# Spine14v1.net
KiCad netlist of a schematic drawn in EAGLE
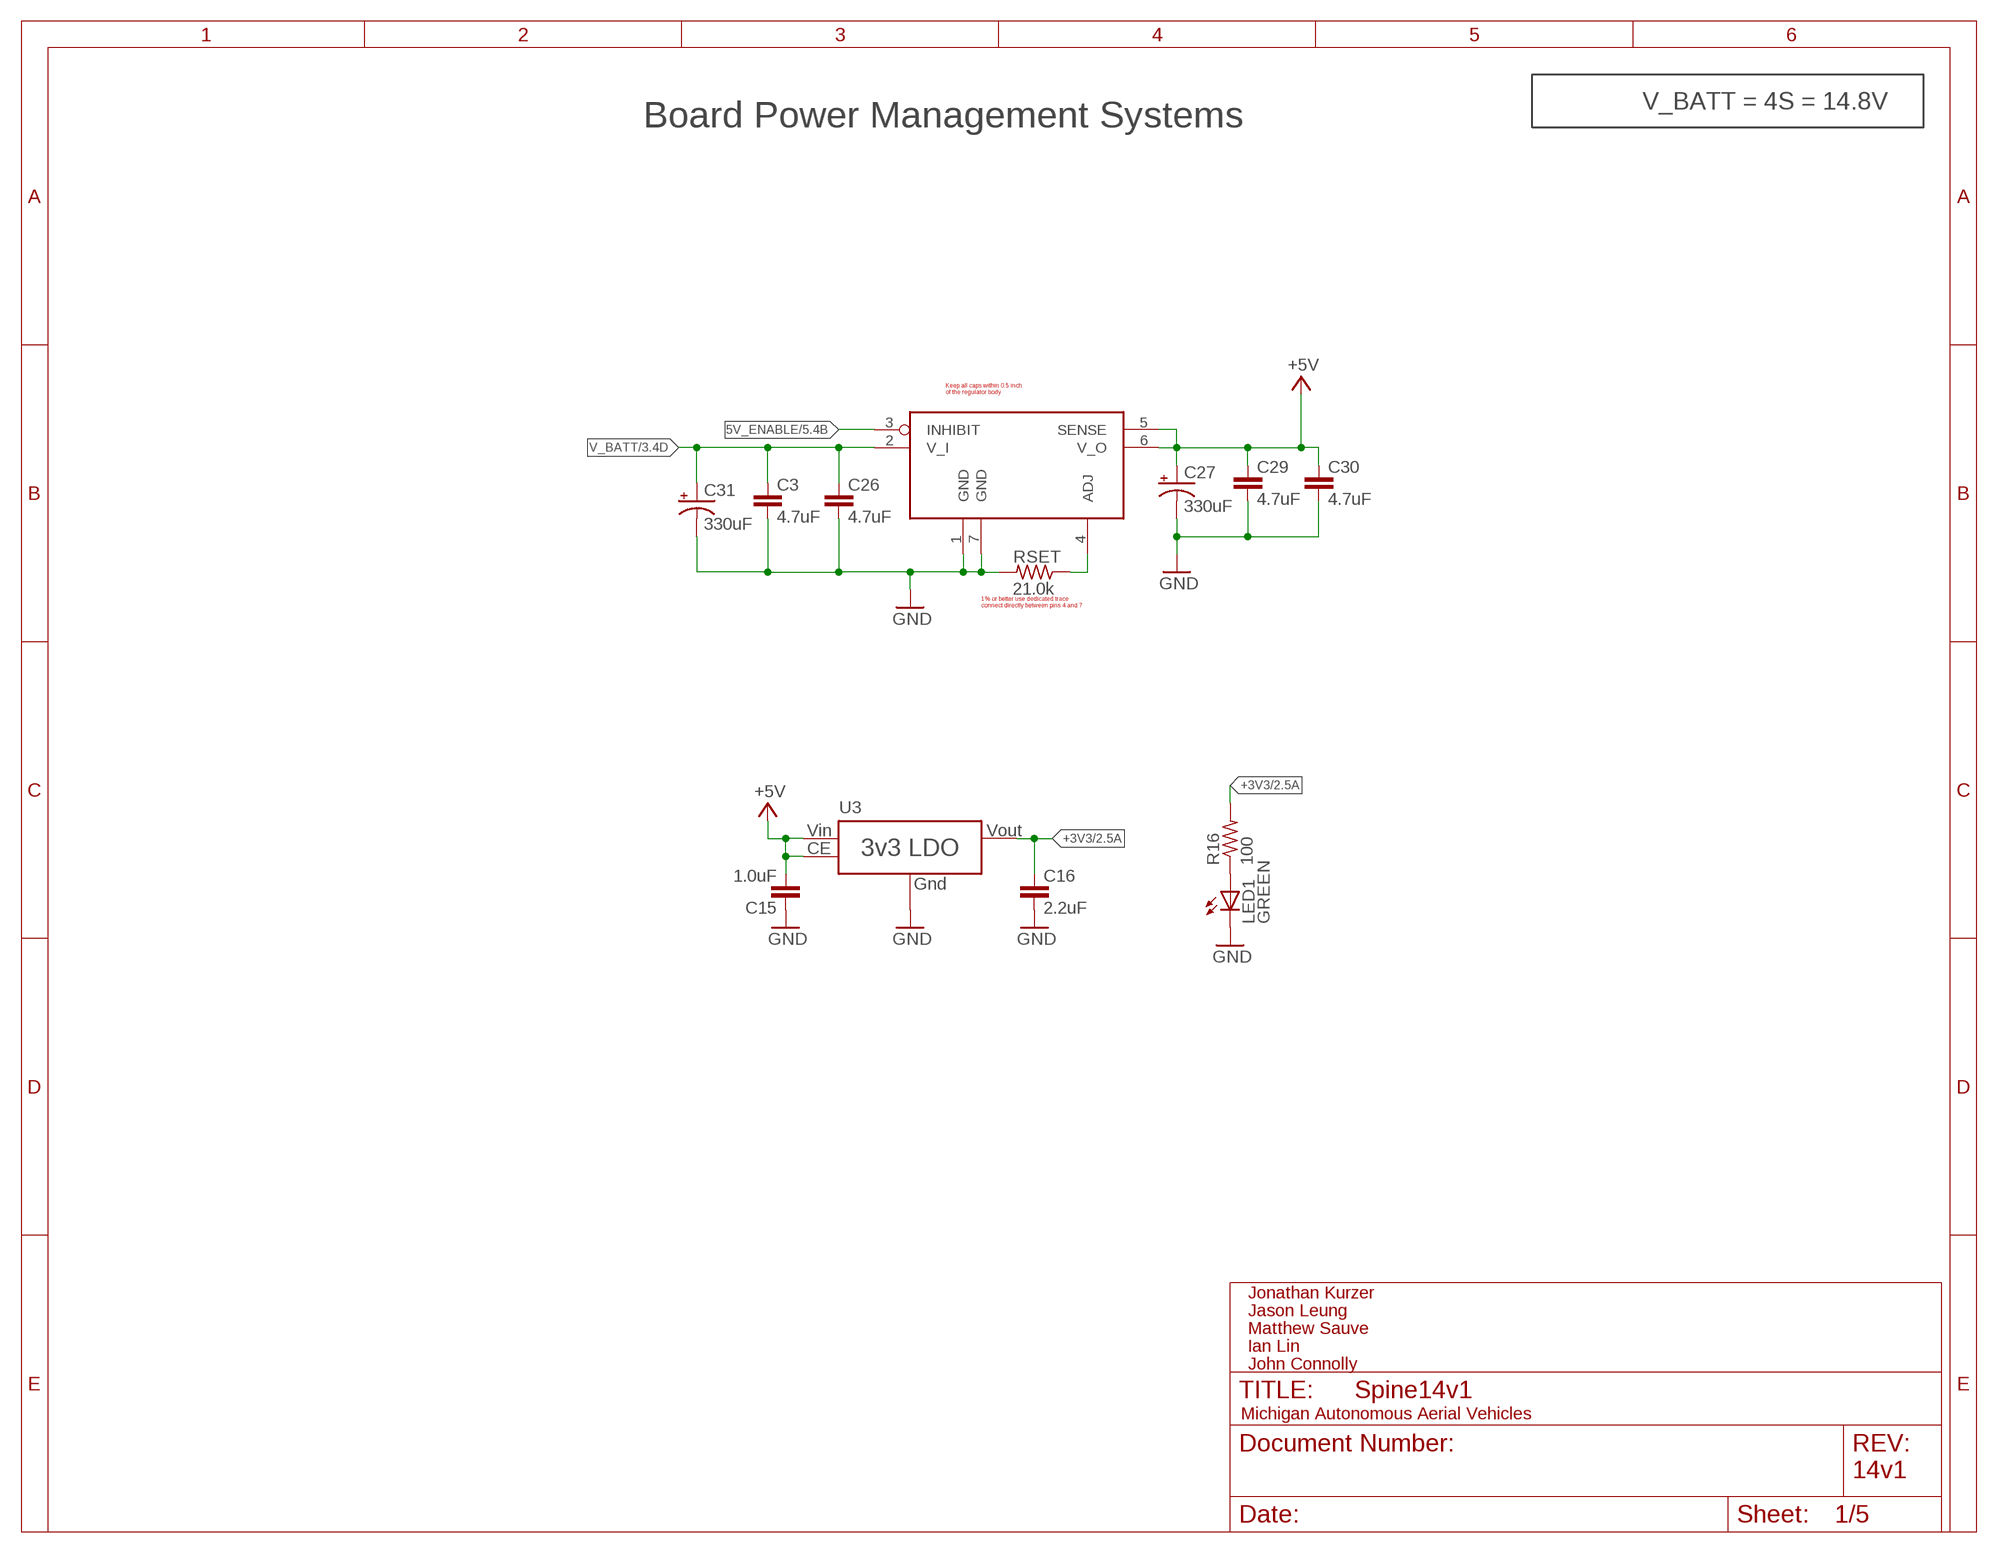
[diagram p0: schematic, sheet 1]
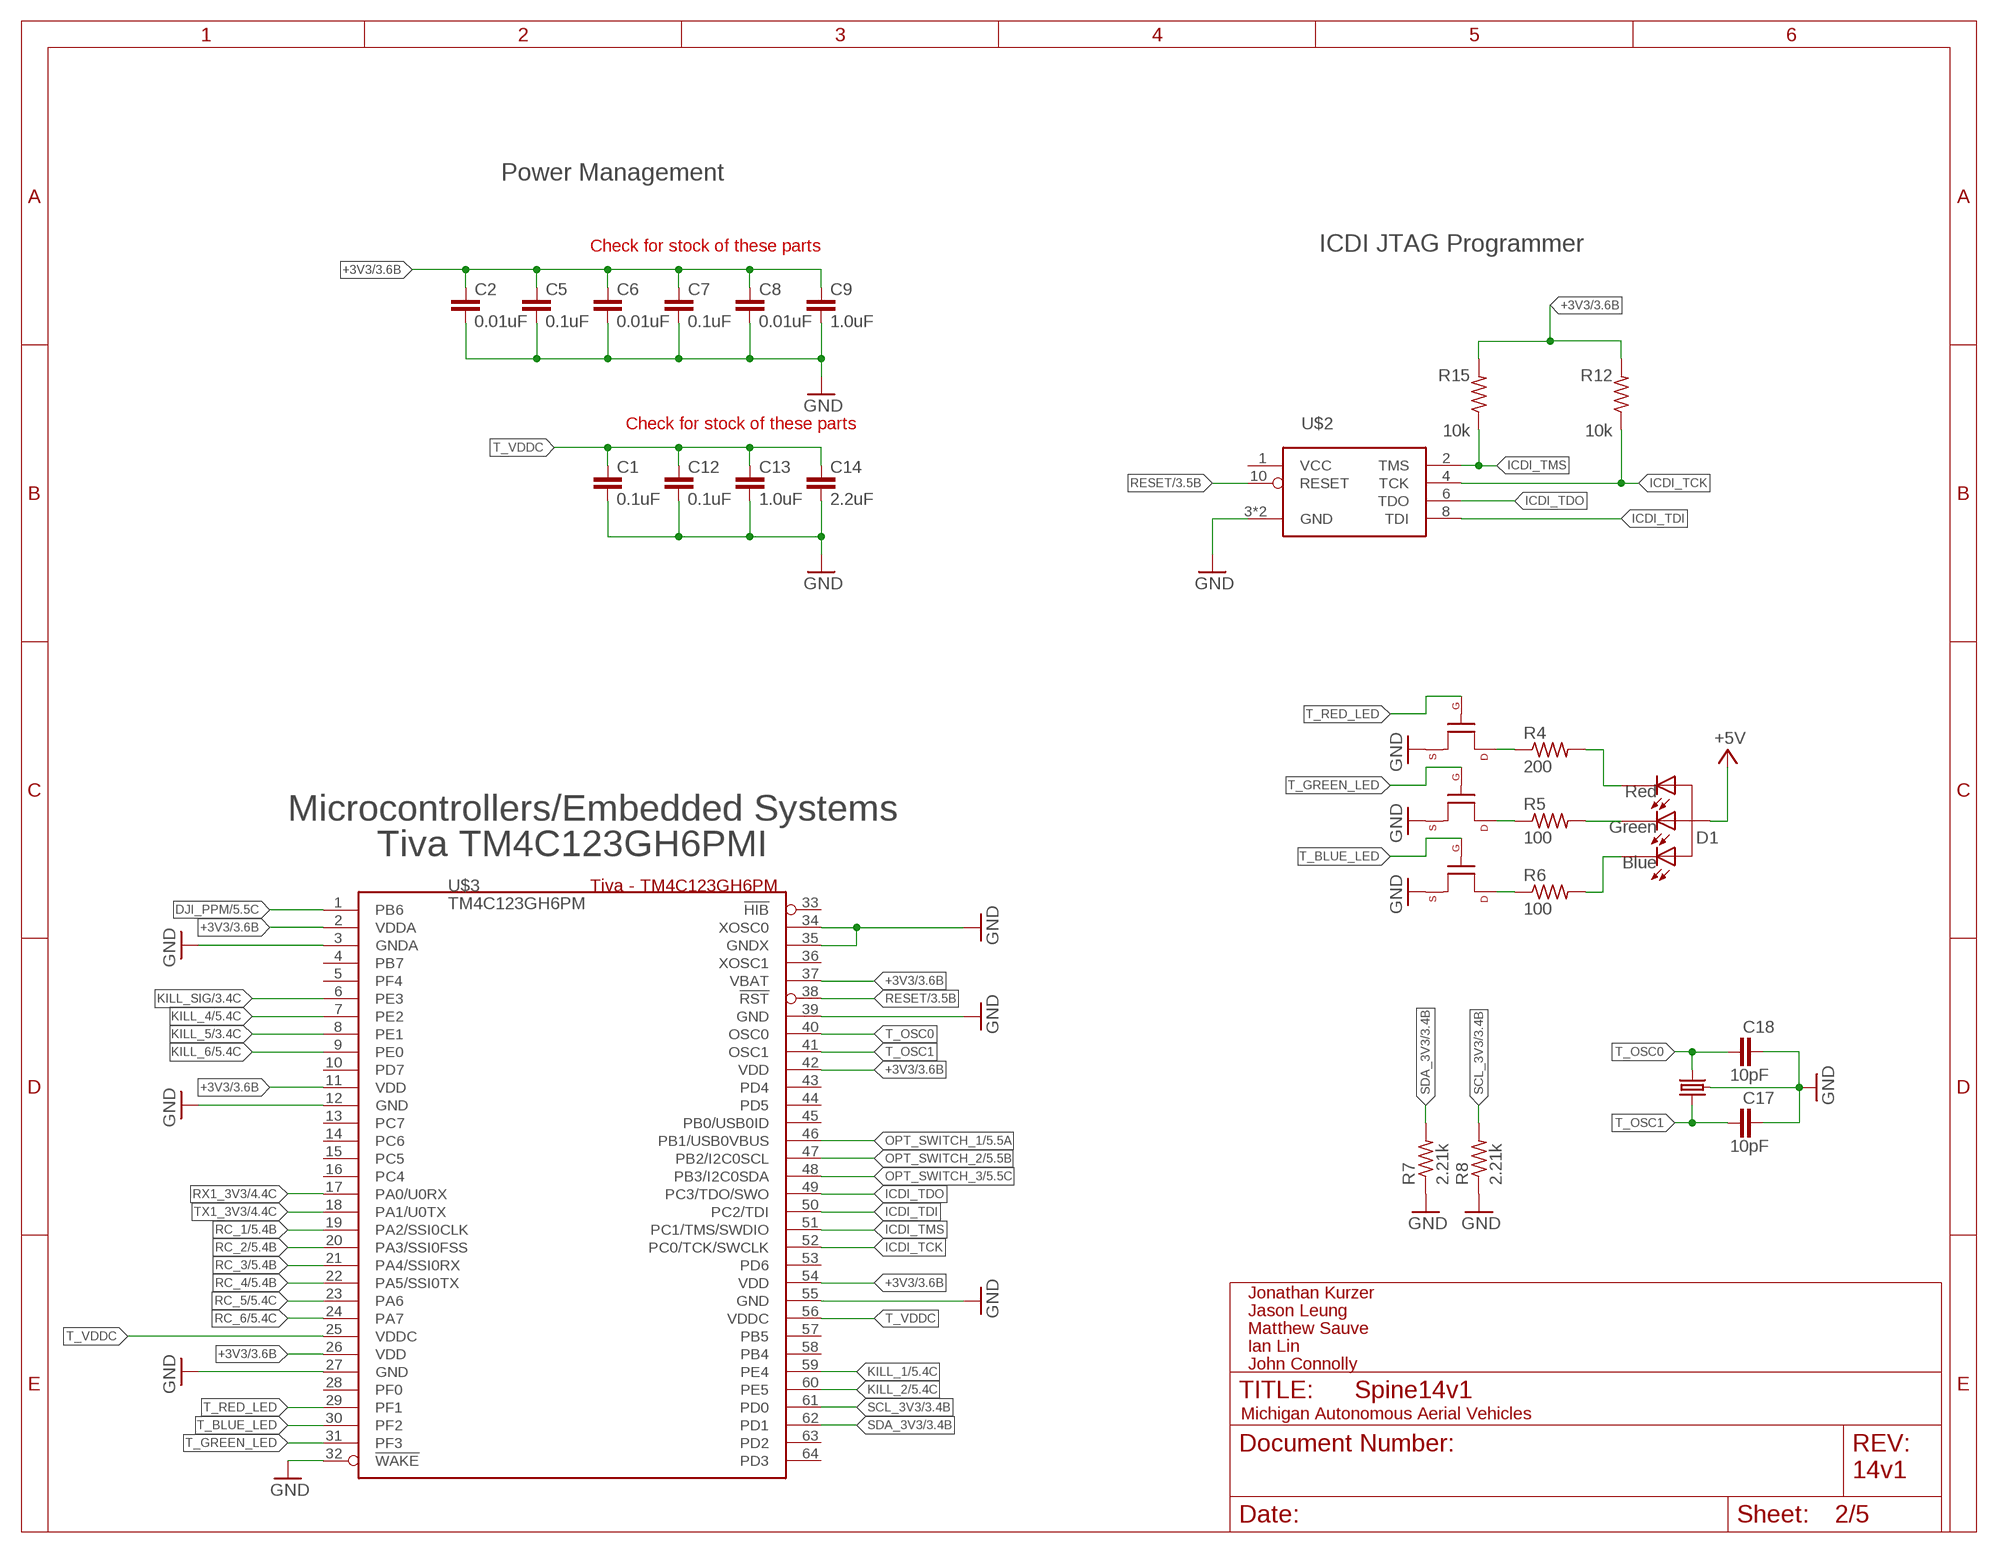
[diagram p1: schematic, sheet 2]
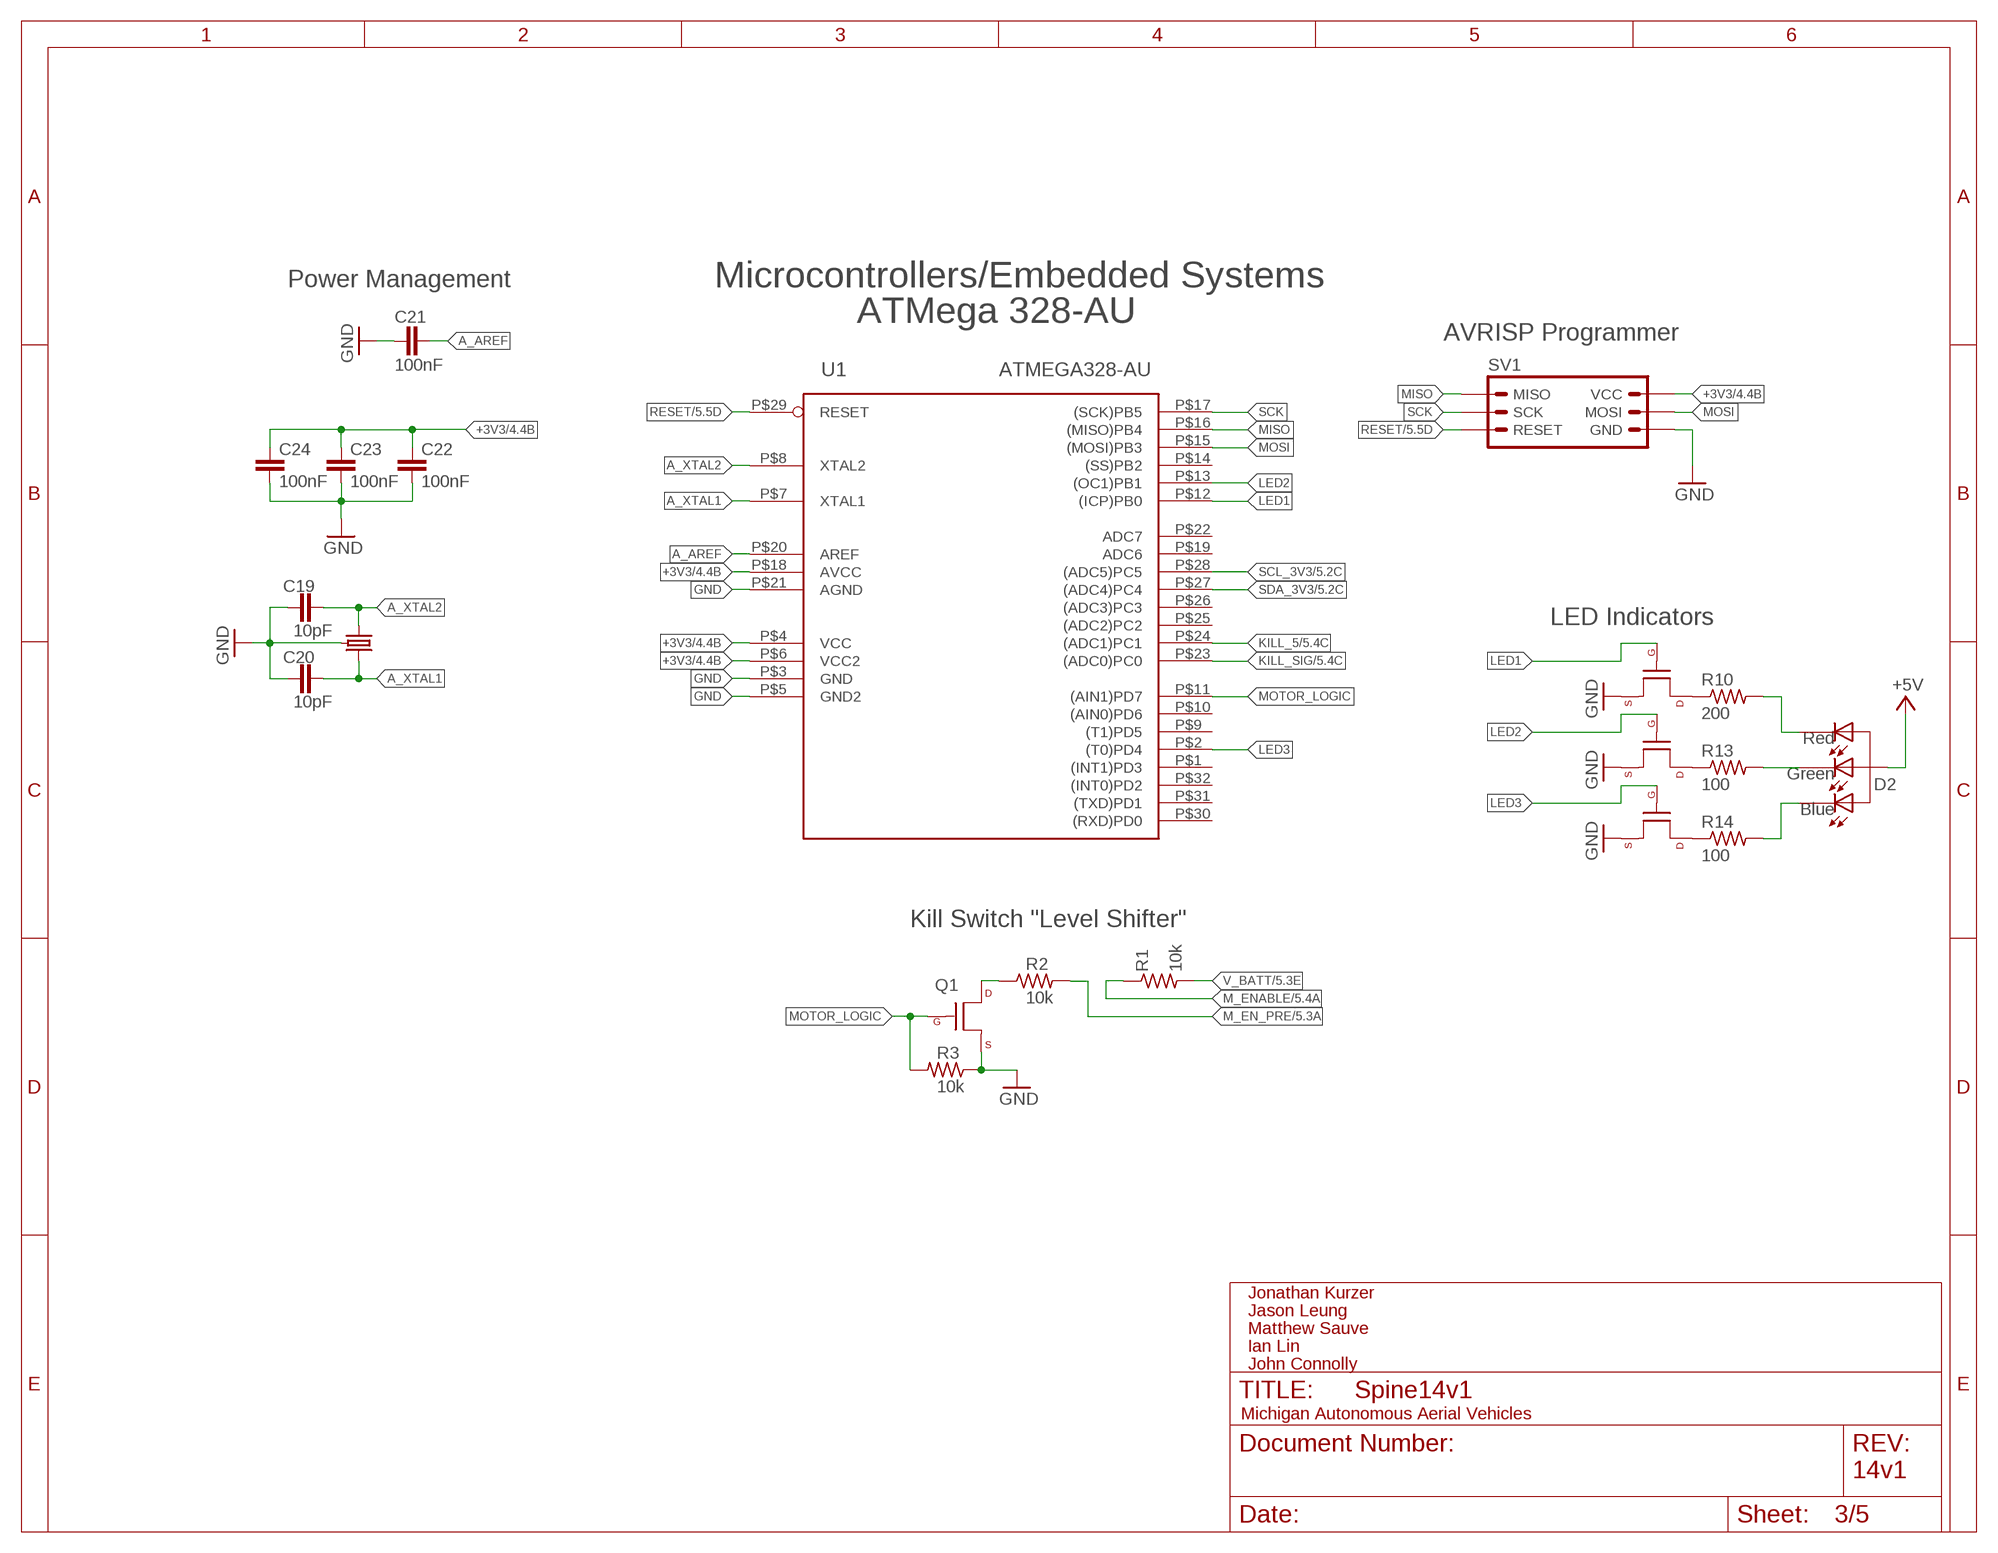
[diagram p2: schematic, sheet 3]
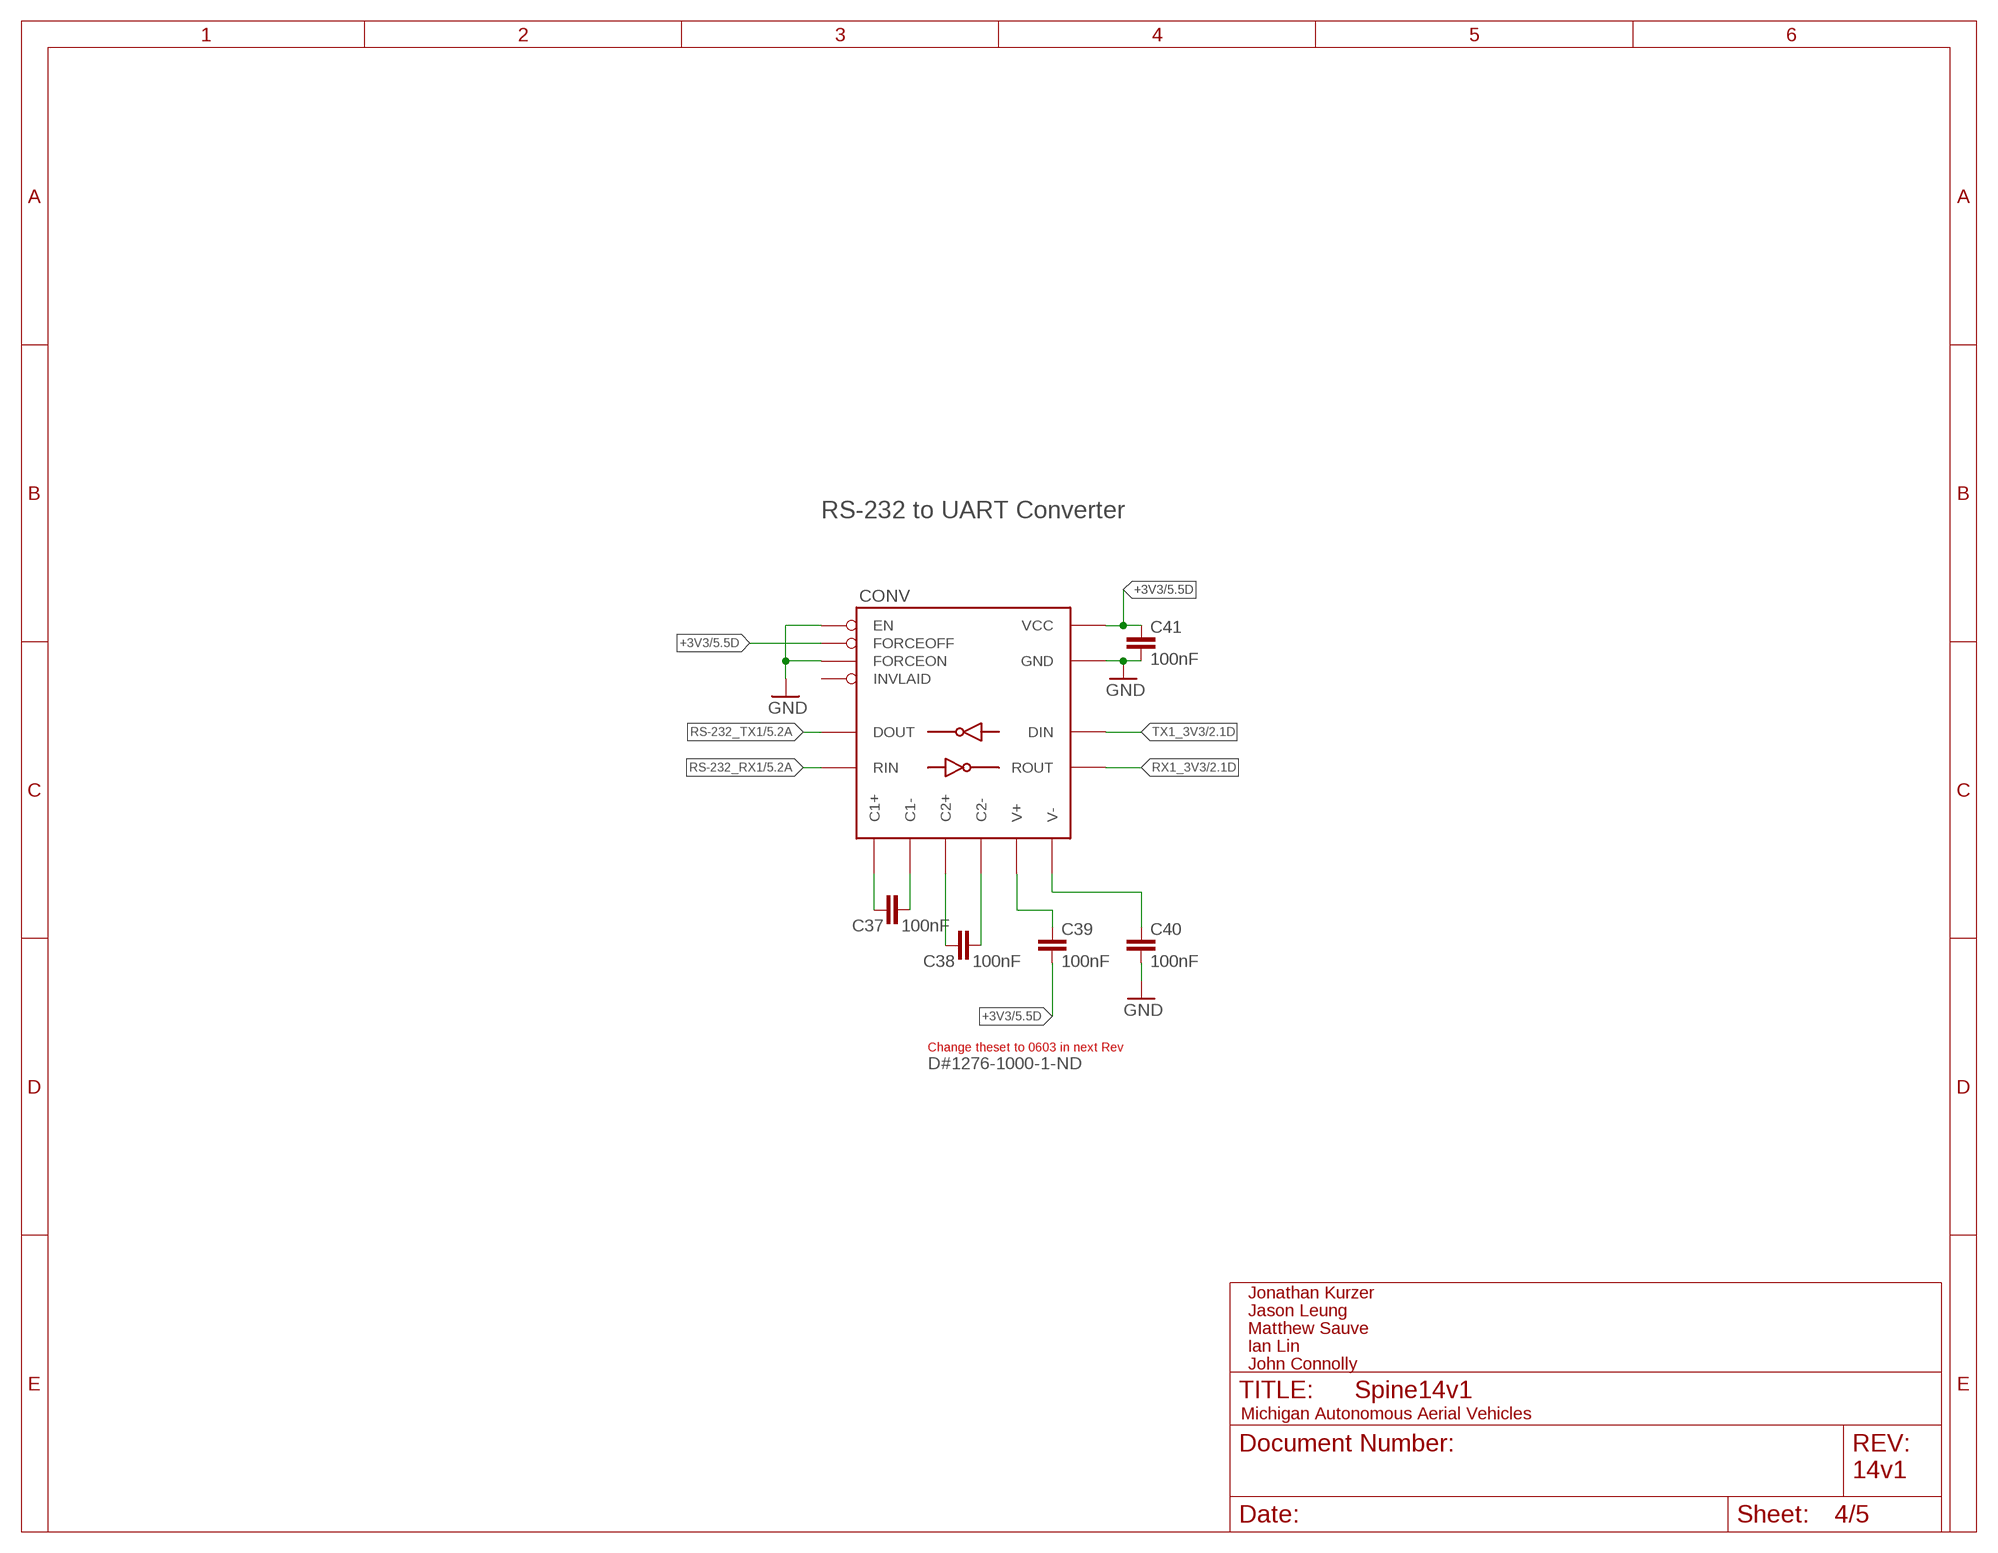
[diagram p3: schematic, sheet 4]
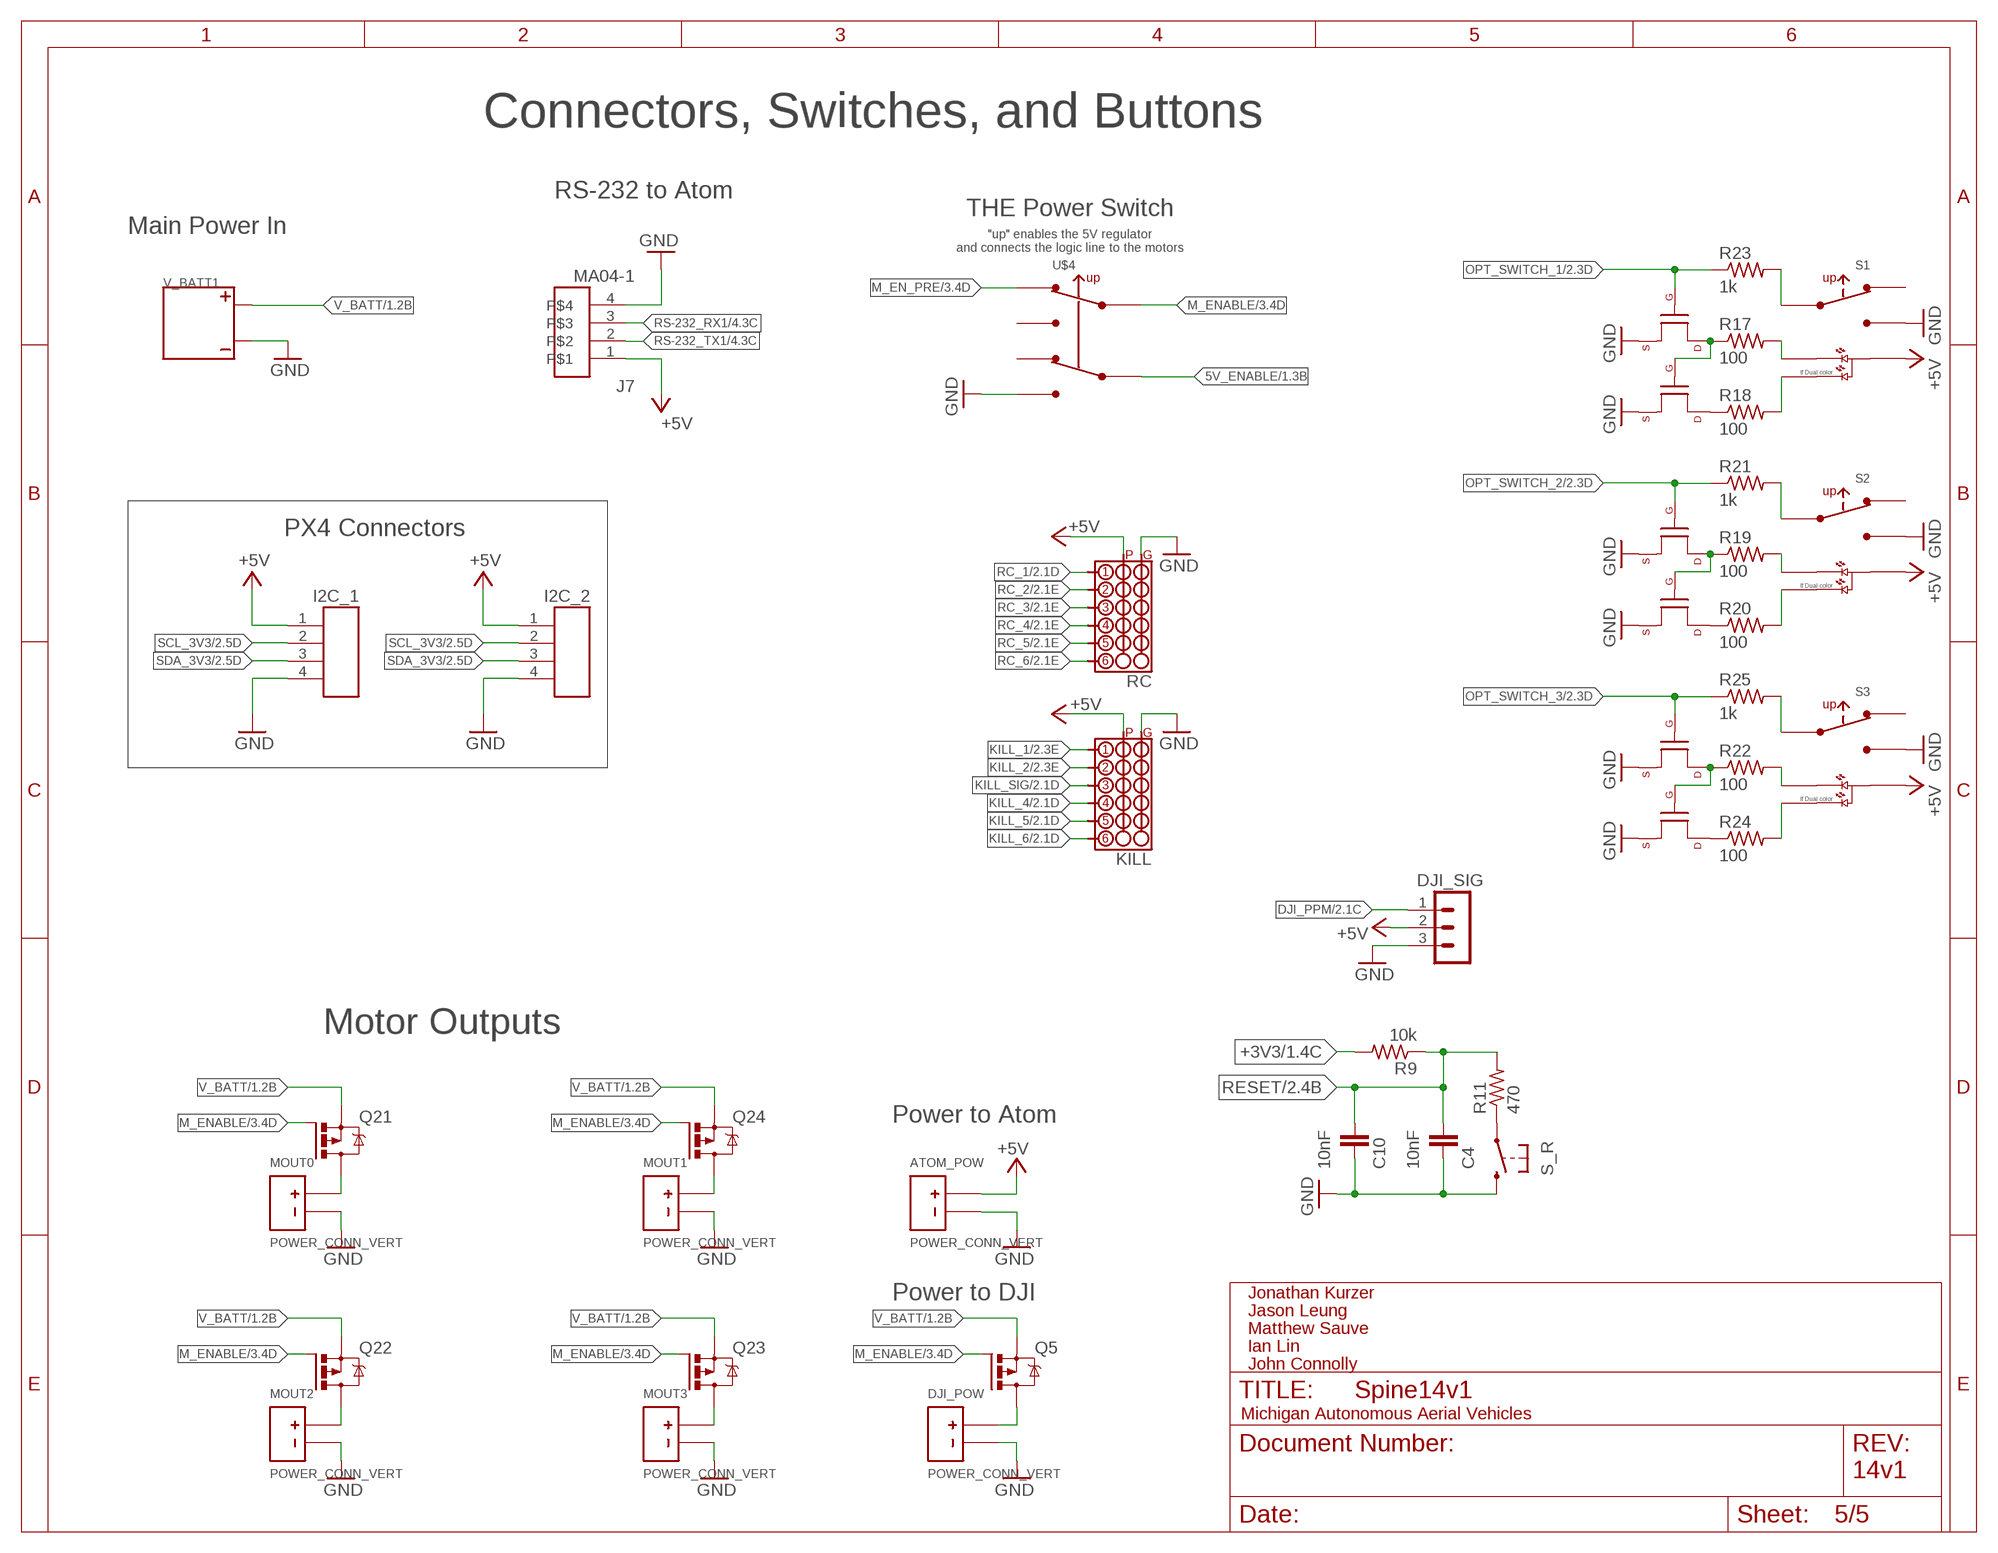
[diagram p4: schematic, sheet 5]

(export (version "E")
  (design (tool "Eeschema 10.0.6"))
  (components
    (comp (ref "C37")
      (value "100nF")
      (footprint "eagle-import:C0603")
      (fields (field (name "DIGIKEY#") "1276-1000-1-ND"))
      (libsource (lib "eagle-import") (part "C-EUC0603"))
    )
    (comp (ref "C38")
      (value "100nF")
      (footprint "eagle-import:C0805")
      (libsource (lib "eagle-import") (part "C-EUC0805"))
    )
    (comp (ref "C39")
      (value "100nF")
      (footprint "eagle-import:C0805")
      (libsource (lib "eagle-import") (part "C-EUC0805"))
    )
    (comp (ref "C40")
      (value "100nF")
      (footprint "eagle-import:C0805")
      (libsource (lib "eagle-import") (part "C-EUC0805"))
    )
    (comp (ref "C41")
      (value "100nF")
      (footprint "eagle-import:C0603")
      (fields (field (name "DIGIKEY#") "1276-1000-1-ND"))
      (libsource (lib "eagle-import") (part "C-EUC0603"))
    )
    (comp (ref "CONV")
      (value "MAX3221-RS232")
      (footprint "eagle-import:16-TSSOP")
      (fields (field (name "DIGIKEY#") "296-19825-1-ND"))
      (libsource (lib "eagle-import") (part "MAX3221-RS232"))
    )
    (comp (ref "ATOM_POW")
      (value "POWER_CONN_VERT")
      (footprint "eagle-import:POWER_CONN")
      (libsource (lib "eagle-import") (part "POWER_CONN_VERT"))
    )
    (comp (ref "C4")
      (value "10nF")
      (footprint "eagle-import:C0603")
      (libsource (lib "eagle-import") (part "C-EUC0603"))
    )
    (comp (ref "C10")
      (value "10nF")
      (footprint "eagle-import:C0603")
      (libsource (lib "eagle-import") (part "C-EUC0603"))
    )
    (comp (ref "DJI_POW")
      (value "POWER_CONN_VERT")
      (footprint "eagle-import:POWER_CONN")
      (libsource (lib "eagle-import") (part "POWER_CONN_VERT"))
    )
    (comp (ref "DJI_SIG")
      (value "MA03-1")
      (footprint "eagle-import:MA03-1")
      (libsource (lib "eagle-import") (part "MA03-1"))
    )
    (comp (ref "I2C_1")
      (value "CONN_HEADER_4POS_RIGHT_ANGLE_I2C")
      (footprint "eagle-import:CONN_HEADER_4POS_1.25MM_SMD")
      (fields (field (name "CONTACT") "D#H12151CT-ND"))
      (libsource (lib "eagle-import") (part "CONN_HEADER_4POS_RIGHT_ANGLE_I2C"))
    )
    (comp (ref "I2C_2")
      (value "CONN_HEADER_4POS_RIGHT_ANGLE_I2C")
      (footprint "eagle-import:CONN_HEADER_4POS_1.25MM_SMD")
      (fields (field (name "CONTACT") "D#H12151CT-ND"))
      (libsource (lib "eagle-import") (part "CONN_HEADER_4POS_RIGHT_ANGLE_I2C"))
    )
    (comp (ref "J7")
      (value "MA04-1")
      (footprint "eagle-import:MA-04-SMD")
      (libsource (lib "eagle-import") (part "MA04-1"))
    )
    (comp (ref "KILL")
      (value "RC_RECIEVER_RECEP")
      (footprint "eagle-import:RC_RECIEVER_RECEP")
      (libsource (lib "eagle-import") (part "RC_RECIEVER_RECEP"))
    )
    (comp (ref "MOUT0")
      (value "POWER_CONN_VERT")
      (footprint "eagle-import:POWER_CONN")
      (libsource (lib "eagle-import") (part "POWER_CONN_VERT"))
    )
    (comp (ref "MOUT1")
      (value "POWER_CONN_VERT")
      (footprint "eagle-import:POWER_CONN")
      (libsource (lib "eagle-import") (part "POWER_CONN_VERT"))
    )
    (comp (ref "MOUT2")
      (value "POWER_CONN_VERT")
      (footprint "eagle-import:POWER_CONN")
      (libsource (lib "eagle-import") (part "POWER_CONN_VERT"))
    )
    (comp (ref "MOUT3")
      (value "POWER_CONN_VERT")
      (footprint "eagle-import:POWER_CONN")
      (libsource (lib "eagle-import") (part "POWER_CONN_VERT"))
    )
    (comp (ref "Q5")
      (value "P-MOSFET-SO8POWER-PAK")
      (footprint "eagle-import:SO-8_POWER-PAK")
      (libsource (lib "eagle-import") (part "P-MOSFET-SO8POWER-PAK"))
    )
    (comp (ref "Q9")
      (value "MOSFET-NCHANNELSMD")
      (footprint "eagle-import:SOT23-3")
      (fields (field (name "DIGIKEY#") "BSN20-7DICT-ND"))
      (libsource (lib "eagle-import") (part "MOSFET-NCHANNELSMD"))
    )
    (comp (ref "Q10")
      (value "MOSFET-NCHANNELSMD")
      (footprint "eagle-import:SOT23-3")
      (fields (field (name "DIGIKEY#") "BSN20-7DICT-ND"))
      (libsource (lib "eagle-import") (part "MOSFET-NCHANNELSMD"))
    )
    (comp (ref "Q11")
      (value "MOSFET-NCHANNELSMD")
      (footprint "eagle-import:SOT23-3")
      (fields (field (name "DIGIKEY#") "BSN20-7DICT-ND"))
      (libsource (lib "eagle-import") (part "MOSFET-NCHANNELSMD"))
    )
    (comp (ref "Q12")
      (value "MOSFET-NCHANNELSMD")
      (footprint "eagle-import:SOT23-3")
      (fields (field (name "DIGIKEY#") "BSN20-7DICT-ND"))
      (libsource (lib "eagle-import") (part "MOSFET-NCHANNELSMD"))
    )
    (comp (ref "Q13")
      (value "MOSFET-NCHANNELSMD")
      (footprint "eagle-import:SOT23-3")
      (fields (field (name "DIGIKEY#") "BSN20-7DICT-ND"))
      (libsource (lib "eagle-import") (part "MOSFET-NCHANNELSMD"))
    )
    (comp (ref "Q14")
      (value "MOSFET-NCHANNELSMD")
      (footprint "eagle-import:SOT23-3")
      (fields (field (name "DIGIKEY#") "BSN20-7DICT-ND"))
      (libsource (lib "eagle-import") (part "MOSFET-NCHANNELSMD"))
    )
    (comp (ref "Q21")
      (value "P-MOSFET-SO8POWER-PAK")
      (footprint "eagle-import:SO-8_POWER-PAK")
      (libsource (lib "eagle-import") (part "P-MOSFET-SO8POWER-PAK"))
    )
    (comp (ref "Q22")
      (value "P-MOSFET-SO8POWER-PAK")
      (footprint "eagle-import:SO-8_POWER-PAK")
      (libsource (lib "eagle-import") (part "P-MOSFET-SO8POWER-PAK"))
    )
    (comp (ref "Q23")
      (value "P-MOSFET-SO8POWER-PAK")
      (footprint "eagle-import:SO-8_POWER-PAK")
      (libsource (lib "eagle-import") (part "P-MOSFET-SO8POWER-PAK"))
    )
    (comp (ref "Q24")
      (value "P-MOSFET-SO8POWER-PAK")
      (footprint "eagle-import:SO-8_POWER-PAK")
      (libsource (lib "eagle-import") (part "P-MOSFET-SO8POWER-PAK"))
    )
    (comp (ref "R9")
      (value "10k")
      (footprint "eagle-import:R0603")
      (libsource (lib "eagle-import") (part "R-USR0603"))
    )
    (comp (ref "R11")
      (value "470")
      (footprint "eagle-import:R0603")
      (libsource (lib "eagle-import") (part "R-USR0603"))
    )
    (comp (ref "R17")
      (value "100")
      (footprint "eagle-import:R0603")
      (libsource (lib "eagle-import") (part "R-USR0603"))
    )
    (comp (ref "R18")
      (value "100")
      (footprint "eagle-import:R0603")
      (libsource (lib "eagle-import") (part "R-USR0603"))
    )
    (comp (ref "R19")
      (value "100")
      (footprint "eagle-import:R0603")
      (libsource (lib "eagle-import") (part "R-USR0603"))
    )
    (comp (ref "R20")
      (value "100")
      (footprint "eagle-import:R0603")
      (libsource (lib "eagle-import") (part "R-USR0603"))
    )
    (comp (ref "R21")
      (value "1k")
      (footprint "eagle-import:R0603")
      (libsource (lib "eagle-import") (part "R-USR0603"))
    )
    (comp (ref "R22")
      (value "100")
      (footprint "eagle-import:R0603")
      (libsource (lib "eagle-import") (part "R-USR0603"))
    )
    (comp (ref "R23")
      (value "1k")
      (footprint "eagle-import:R0603")
      (libsource (lib "eagle-import") (part "R-USR0603"))
    )
    (comp (ref "R24")
      (value "100")
      (footprint "eagle-import:R0603")
      (libsource (lib "eagle-import") (part "R-USR0603"))
    )
    (comp (ref "R25")
      (value "1k")
      (footprint "eagle-import:R0603")
      (libsource (lib "eagle-import") (part "R-USR0603"))
    )
    (comp (ref "RC")
      (value "RC_RECIEVER_RECEP")
      (footprint "eagle-import:RC_RECIEVER_RECEP")
      (libsource (lib "eagle-import") (part "RC_RECIEVER_RECEP"))
    )
    (comp (ref "S1")
      (value "SWITCH_SPDT_ILUMINATED_2COLOR_VERT_ILLUMINATED")
      (footprint "eagle-import:NKK_VERT_SWITCH_6PIN")
      (libsource (lib "eagle-import") (part "SWITCH_SPDT_ILUMINATED_2COLOR_VERT_ILLUMINATED"))
    )
    (comp (ref "S2")
      (value "SWITCH_SPDT_ILUMINATED_2COLOR_VERT_ILLUMINATED")
      (footprint "eagle-import:NKK_VERT_SWITCH_6PIN")
      (libsource (lib "eagle-import") (part "SWITCH_SPDT_ILUMINATED_2COLOR_VERT_ILLUMINATED"))
    )
    (comp (ref "S3")
      (value "SWITCH_SPDT_ILUMINATED_2COLOR_VERT_ILLUMINATED")
      (footprint "eagle-import:NKK_VERT_SWITCH_6PIN")
      (libsource (lib "eagle-import") (part "SWITCH_SPDT_ILUMINATED_2COLOR_VERT_ILLUMINATED"))
    )
    (comp (ref "S_R")
      (value "TACT_BUTTONSMD")
      (footprint "eagle-import:TACT-MOM-SMD")
      (libsource (lib "eagle-import") (part "TACT_BUTTONSMD"))
    )
    (comp (ref "U$4")
      (value "JON_LIB_SWITCH_DPDT")
      (footprint "eagle-import:JON_LIB_SWITCH_VERT_DPDT")
      (libsource (lib "eagle-import") (part "JON_LIB_SWITCH_DPDT"))
    )
    (comp (ref "V_BATT1")
      (value "BATT-CONN-50A_MINI-FIT-SR_THRU-HOLE")
      (footprint "eagle-import:BATT-CONN-50A")
      (libsource (lib "eagle-import") (part "BATT-CONN-50A_MINI-FIT-SR_THRU-HOLE"))
    )
    (comp (ref "C1")
      (value "0.1uF")
      (footprint "eagle-import:C0603")
      (libsource (lib "eagle-import") (part "C-EUC0603"))
    )
    (comp (ref "C2")
      (value "0.01uF")
      (footprint "eagle-import:C0603")
      (libsource (lib "eagle-import") (part "C-EUC0603"))
    )
    (comp (ref "C5")
      (value "0.1uF")
      (footprint "eagle-import:C0603")
      (libsource (lib "eagle-import") (part "C-EUC0603"))
    )
    (comp (ref "C6")
      (value "0.01uF")
      (footprint "eagle-import:C0603")
      (libsource (lib "eagle-import") (part "C-EUC0603"))
    )
    (comp (ref "C7")
      (value "0.1uF")
      (footprint "eagle-import:C0603")
      (libsource (lib "eagle-import") (part "C-EUC0603"))
    )
    (comp (ref "C8")
      (value "0.01uF")
      (footprint "eagle-import:C0603")
      (libsource (lib "eagle-import") (part "C-EUC0603"))
    )
    (comp (ref "C9")
      (value "1.0uF")
      (footprint "eagle-import:C0603")
      (libsource (lib "eagle-import") (part "C-EUC0603"))
    )
    (comp (ref "C12")
      (value "0.1uF")
      (footprint "eagle-import:C0603")
      (libsource (lib "eagle-import") (part "C-EUC0603"))
    )
    (comp (ref "C13")
      (value "1.0uF")
      (footprint "eagle-import:C0805")
      (libsource (lib "eagle-import") (part "C-EUC0805"))
    )
    (comp (ref "C14")
      (value "2.2uF")
      (footprint "eagle-import:C0805")
      (libsource (lib "eagle-import") (part "C-EUC0805"))
    )
    (comp (ref "C17")
      (value "10pF")
      (footprint "eagle-import:C0603")
      (fields (field (name "DIGIKEY#") "399-1049-1-ND"))
      (libsource (lib "eagle-import") (part "C-EUC0603"))
    )
    (comp (ref "C18")
      (value "10pF")
      (footprint "eagle-import:C0603")
      (fields (field (name "DIGIKEY#") "399-1049-1-ND"))
      (libsource (lib "eagle-import") (part "C-EUC0603"))
    )
    (comp (ref "D1")
      (value "LED_RGB_CA")
      (footprint "eagle-import:LED_RGB_0606")
      (libsource (lib "eagle-import") (part "LED_RGB_CA"))
    )
    (comp (ref "Q2")
      (value "MOSFET-NCHANNELSMD")
      (footprint "eagle-import:SOT23-3")
      (fields (field (name "DIGIKEY#") "BSN20-7DICT-ND"))
      (libsource (lib "eagle-import") (part "MOSFET-NCHANNELSMD"))
    )
    (comp (ref "Q3")
      (value "MOSFET-NCHANNELSMD")
      (footprint "eagle-import:SOT23-3")
      (fields (field (name "DIGIKEY#") "BSN20-7DICT-ND"))
      (libsource (lib "eagle-import") (part "MOSFET-NCHANNELSMD"))
    )
    (comp (ref "Q4")
      (value "MOSFET-NCHANNELSMD")
      (footprint "eagle-import:SOT23-3")
      (fields (field (name "DIGIKEY#") "BSN20-7DICT-ND"))
      (libsource (lib "eagle-import") (part "MOSFET-NCHANNELSMD"))
    )
    (comp (ref "R4")
      (value "200")
      (footprint "eagle-import:R0603")
      (libsource (lib "eagle-import") (part "R-USR0603"))
    )
    (comp (ref "R5")
      (value "100")
      (footprint "eagle-import:R0603")
      (libsource (lib "eagle-import") (part "R-USR0603"))
    )
    (comp (ref "R6")
      (value "100")
      (footprint "eagle-import:R0603")
      (libsource (lib "eagle-import") (part "R-USR0603"))
    )
    (comp (ref "R7")
      (value "2.21k")
      (footprint "eagle-import:R0603")
      (libsource (lib "eagle-import") (part "R-USR0603"))
    )
    (comp (ref "R8")
      (value "2.21k")
      (footprint "eagle-import:R0603")
      (libsource (lib "eagle-import") (part "R-USR0603"))
    )
    (comp (ref "R12")
      (value "10k")
      (footprint "eagle-import:R0603")
      (libsource (lib "eagle-import") (part "R-USR0603"))
    )
    (comp (ref "R15")
      (value "10k")
      (footprint "eagle-import:R0603")
      (libsource (lib "eagle-import") (part "R-USR0603"))
    )
    (comp (ref "U$1")
      (value "CRYSTAL_403C11E16")
      (footprint "eagle-import:4-SMD-SWITCH")
      (libsource (lib "eagle-import") (part "CRYSTAL_403C11E16"))
    )
    (comp (ref "U$2")
      (value "JTAG-ARM_TC-10")
      (footprint "eagle-import:TC2050-IDC")
      (libsource (lib "eagle-import") (part "JTAG-ARM_TC-10"))
    )
    (comp (ref "U$3")
      (value "TM4C123GH6PM")
      (footprint "eagle-import:TM4C123GH6PM")
      (libsource (lib "eagle-import") (part "TM4C123GH6PM"))
    )
    (comp (ref "C19")
      (value "10pF")
      (footprint "eagle-import:C0603")
      (fields (field (name "DIGIKEY#") "399-1049-1-ND"))
      (libsource (lib "eagle-import") (part "C-EUC0603"))
    )
    (comp (ref "C20")
      (value "10pF")
      (footprint "eagle-import:C0603")
      (fields (field (name "DIGIKEY#") "399-1049-1-ND"))
      (libsource (lib "eagle-import") (part "C-EUC0603"))
    )
    (comp (ref "C21")
      (value "100nF")
      (footprint "eagle-import:C0603")
      (fields (field (name "DIGIKEY#") "1276-1000-1-ND"))
      (libsource (lib "eagle-import") (part "C-EUC0603"))
    )
    (comp (ref "C22")
      (value "100nF")
      (footprint "eagle-import:C0603")
      (fields (field (name "DIGIKEY#") "1276-1000-1-ND"))
      (libsource (lib "eagle-import") (part "C-EUC0603"))
    )
    (comp (ref "C23")
      (value "100nF")
      (footprint "eagle-import:C0603")
      (fields (field (name "DIGIKEY#") "1276-1000-1-ND"))
      (libsource (lib "eagle-import") (part "C-EUC0603"))
    )
    (comp (ref "C24")
      (value "100nF")
      (footprint "eagle-import:C0603")
      (fields (field (name "DIGIKEY#") "1276-1000-1-ND"))
      (libsource (lib "eagle-import") (part "C-EUC0603"))
    )
    (comp (ref "D2")
      (value "LED_RGB_CA")
      (footprint "eagle-import:LED_RGB_0606")
      (libsource (lib "eagle-import") (part "LED_RGB_CA"))
    )
    (comp (ref "Q1")
      (value "MOSFET-NCHANNELSMD")
      (footprint "eagle-import:SOT23-3")
      (fields (field (name "DIGIKEY#") "BSN20-7DICT-ND"))
      (libsource (lib "eagle-import") (part "MOSFET-NCHANNELSMD"))
    )
    (comp (ref "Q6")
      (value "MOSFET-NCHANNELSMD")
      (footprint "eagle-import:SOT23-3")
      (fields (field (name "DIGIKEY#") "BSN20-7DICT-ND"))
      (libsource (lib "eagle-import") (part "MOSFET-NCHANNELSMD"))
    )
    (comp (ref "Q7")
      (value "MOSFET-NCHANNELSMD")
      (footprint "eagle-import:SOT23-3")
      (fields (field (name "DIGIKEY#") "BSN20-7DICT-ND"))
      (libsource (lib "eagle-import") (part "MOSFET-NCHANNELSMD"))
    )
    (comp (ref "Q8")
      (value "MOSFET-NCHANNELSMD")
      (footprint "eagle-import:SOT23-3")
      (fields (field (name "DIGIKEY#") "BSN20-7DICT-ND"))
      (libsource (lib "eagle-import") (part "MOSFET-NCHANNELSMD"))
    )
    (comp (ref "R1")
      (value "10k")
      (footprint "eagle-import:R0603")
      (libsource (lib "eagle-import") (part "R-USR0603"))
    )
    (comp (ref "R2")
      (value "10k")
      (footprint "eagle-import:R0603")
      (libsource (lib "eagle-import") (part "R-USR0603"))
    )
    (comp (ref "R3")
      (value "10k")
      (footprint "eagle-import:R0603")
      (libsource (lib "eagle-import") (part "R-USR0603"))
    )
    (comp (ref "R10")
      (value "200")
      (footprint "eagle-import:R0603")
      (libsource (lib "eagle-import") (part "R-USR0603"))
    )
    (comp (ref "R13")
      (value "100")
      (footprint "eagle-import:R0603")
      (libsource (lib "eagle-import") (part "R-USR0603"))
    )
    (comp (ref "R14")
      (value "100")
      (footprint "eagle-import:R0603")
      (libsource (lib "eagle-import") (part "R-USR0603"))
    )
    (comp (ref "SV1")
      (value "AVRISP-6_3X2_PLUG_OF_NAILS")
      (footprint "eagle-import:TC2030-IDC")
      (libsource (lib "eagle-import") (part "AVRISP-6_3X2_PLUG_OF_NAILS"))
    )
    (comp (ref "U$6")
      (value "CRYSTAL_403C11E16")
      (footprint "eagle-import:4-SMD-SWITCH")
      (libsource (lib "eagle-import") (part "CRYSTAL_403C11E16"))
    )
    (comp (ref "U1")
      (value "ATMEGA328-AU")
      (footprint "eagle-import:32-TQFP")
      (libsource (lib "eagle-import") (part "ATMEGA328-AU"))
    )
    (comp (ref "C3")
      (value "4.7uF")
      (footprint "eagle-import:C1206")
      (fields (field (name "DIGIKEY#") "587-2994-1-ND"))
      (libsource (lib "eagle-import") (part "C-EUC1206"))
    )
    (comp (ref "C15")
      (value "1.0uF")
      (footprint "eagle-import:C0805")
      (libsource (lib "eagle-import") (part "C-EUC0805"))
    )
    (comp (ref "C16")
      (value "2.2uF")
      (footprint "eagle-import:C0805")
      (libsource (lib "eagle-import") (part "C-EUC0805"))
    )
    (comp (ref "C26")
      (value "4.7uF")
      (footprint "eagle-import:C1206")
      (fields (field (name "DIGIKEY#") "587-2994-1-ND"))
      (libsource (lib "eagle-import") (part "C-EUC1206"))
    )
    (comp (ref "C27")
      (value "330uF")
      (footprint "eagle-import:PANASONIC_F")
      (libsource (lib "eagle-import") (part "CPOL-USF"))
    )
    (comp (ref "C29")
      (value "4.7uF")
      (footprint "eagle-import:C1206")
      (fields (field (name "DIGIKEY#") "587-2994-1-ND"))
      (libsource (lib "eagle-import") (part "C-EUC1206"))
    )
    (comp (ref "C30")
      (value "4.7uF")
      (footprint "eagle-import:C1206")
      (fields (field (name "DIGIKEY#") "587-2994-1-ND"))
      (libsource (lib "eagle-import") (part "C-EUC1206"))
    )
    (comp (ref "C31")
      (value "330uF")
      (footprint "eagle-import:PANASONIC_F")
      (libsource (lib "eagle-import") (part "CPOL-USF"))
    )
    (comp (ref "LED1")
      (value "GREEN")
      (footprint "eagle-import:CHIPLED_0603")
      (libsource (lib "eagle-import") (part "LEDCHIPLED_0603"))
    )
    (comp (ref "R16")
      (value "100")
      (footprint "eagle-import:R0603")
      (libsource (lib "eagle-import") (part "R-USR0603"))
    )
    (comp (ref "RSET")
      (value "21.0k")
      (footprint "eagle-import:R0603")
      (libsource (lib "eagle-import") (part "R-USR0603"))
    )
    (comp (ref "U$5")
      (value "POWER-MODULE-TI-6A_SOLDERLESS_TERMINAL")
      (footprint "eagle-import:POWER-MOD-TI-6A-SOLDERLESS-TERMINAL")
      (libsource (lib "eagle-import") (part "POWER-MODULE-TI-6A_SOLDERLESS_TERMINAL"))
    )
    (comp (ref "U3")
      (value "XC6210")
      (footprint "eagle-import:SOT-25")
      (libsource (lib "eagle-import") (part "XC6210"))
    )
  )
  (nets
    (net (code "1") (name "+3V3") (class "Default")
      (node (ref "C16") (pin "1") (pinfunction "1_1") (pintype "passive"))
      (node (ref "C2") (pin "1") (pinfunction "1_1") (pintype "passive"))
      (node (ref "C22") (pin "1") (pinfunction "1_1") (pintype "passive"))
      (node (ref "C23") (pin "1") (pinfunction "1_1") (pintype "passive"))
      (node (ref "C24") (pin "1") (pinfunction "1_1") (pintype "passive"))
      (node (ref "C39") (pin "2") (pinfunction "2_2") (pintype "passive"))
      (node (ref "C41") (pin "1") (pinfunction "1_1") (pintype "passive"))
      (node (ref "C5") (pin "1") (pinfunction "1_1") (pintype "passive"))
      (node (ref "C6") (pin "1") (pinfunction "1_1") (pintype "passive"))
      (node (ref "C7") (pin "1") (pinfunction "1_1") (pintype "passive"))
      (node (ref "C8") (pin "1") (pinfunction "1_1") (pintype "passive"))
      (node (ref "C9") (pin "1") (pinfunction "1_1") (pintype "passive"))
      (node (ref "CONV") (pin "P$15") (pinfunction "VCC_P$15") (pintype "power_in"))
      (node (ref "CONV") (pin "P$16") (pinfunction "FORCEOFF_P$16") (pintype "input"))
      (node (ref "R12") (pin "2") (pinfunction "2_2") (pintype "passive"))
      (node (ref "R15") (pin "2") (pinfunction "2_2") (pintype "passive"))
      (node (ref "R16") (pin "2") (pinfunction "2_2") (pintype "passive"))
      (node (ref "R9") (pin "2") (pinfunction "2_2") (pintype "passive"))
      (node (ref "SV1") (pin "6") (pinfunction "VCC_6") (pintype "passive"))
      (node (ref "U$3") (pin "11") (pinfunction "VDD_11") (pintype "bidirectional"))
      (node (ref "U$3") (pin "2") (pinfunction "VDDA_2") (pintype "bidirectional"))
      (node (ref "U$3") (pin "26") (pinfunction "VDD_26") (pintype "bidirectional"))
      (node (ref "U$3") (pin "37") (pinfunction "VBAT_37") (pintype "bidirectional"))
      (node (ref "U$3") (pin "42") (pinfunction "VDD_42") (pintype "bidirectional"))
      (node (ref "U$3") (pin "54") (pinfunction "VDD_54") (pintype "bidirectional"))
      (node (ref "U1") (pin "P$18") (pinfunction "AVCC_P$18") (pintype "bidirectional"))
      (node (ref "U1") (pin "P$4") (pinfunction "VCC_P$4") (pintype "bidirectional"))
      (node (ref "U1") (pin "P$6") (pinfunction "VCC2_P$6") (pintype "bidirectional"))
      (node (ref "U3") (pin "5") (pinfunction "VOUT_5") (pintype "power_in"))
    )
    (net (code "2") (name "+5V") (class "Default")
      (node (ref "ATOM_POW") (pin "P1") (pinfunction "P_P1") (pintype "bidirectional"))
      (node (ref "C15") (pin "2") (pinfunction "2_2") (pintype "passive"))
      (node (ref "C27") (pin "+") (pinfunction "+_+") (pintype "passive"))
      (node (ref "C29") (pin "1") (pinfunction "1_1") (pintype "passive"))
      (node (ref "C30") (pin "1") (pinfunction "1_1") (pintype "passive"))
      (node (ref "D1") (pin "1") (pinfunction "A_1") (pintype "passive"))
      (node (ref "D2") (pin "1") (pinfunction "A_1") (pintype "passive"))
      (node (ref "DJI_SIG") (pin "2") (pinfunction "2_2") (pintype "passive"))
      (node (ref "I2C_1") (pin "1") (pinfunction "P$1_1") (pintype "bidirectional"))
      (node (ref "I2C_2") (pin "1") (pinfunction "P$1_1") (pintype "bidirectional"))
      (node (ref "J7") (pin "1") (pinfunction "P$1_1") (pintype "bidirectional"))
      (node (ref "KILL") (pin "VCC") (pinfunction "VCC_VCC") (pintype "bidirectional"))
      (node (ref "KILL") (pin "VCC2") (pinfunction "VCC_VCC2") (pintype "bidirectional"))
      (node (ref "RC") (pin "VCC") (pinfunction "VCC_VCC") (pintype "bidirectional"))
      (node (ref "RC") (pin "VCC2") (pinfunction "VCC_VCC2") (pintype "bidirectional"))
      (node (ref "S1") (pin "P$5") (pinfunction "P$5_P$5") (pintype "bidirectional"))
      (node (ref "S2") (pin "P$5") (pinfunction "P$5_P$5") (pintype "bidirectional"))
      (node (ref "S3") (pin "P$5") (pinfunction "P$5_P$5") (pintype "bidirectional"))
      (node (ref "U$5") (pin "5") (pinfunction "SENSE_5") (pintype "input"))
      (node (ref "U$5") (pin "6") (pinfunction "V_O_6") (pintype "output"))
      (node (ref "U3") (pin "1") (pinfunction "VIN_1") (pintype "power_in"))
      (node (ref "U3") (pin "3") (pinfunction "CE_3") (pintype "input"))
    )
    (net (code "3") (name "5V_ENABLE") (class "Default")
      (node (ref "U$4") (pin "P$5") (pinfunction "P$5_P$5") (pintype "bidirectional"))
      (node (ref "U$5") (pin "3") (pinfunction "INHIBIT_3") (pintype "passive"))
    )
    (net (code "4") (name "A_AREF") (class "Default")
      (node (ref "C21") (pin "1") (pinfunction "1_1") (pintype "passive"))
      (node (ref "U1") (pin "P$20") (pinfunction "AREF_P$20") (pintype "bidirectional"))
    )
    (net (code "5") (name "A_XTAL1") (class "Default")
      (node (ref "C20") (pin "2") (pinfunction "2_2") (pintype "passive"))
      (node (ref "U$6") (pin "3") (pinfunction "2_3") (pintype "bidirectional"))
      (node (ref "U1") (pin "P$7") (pinfunction "XTAL1_P$7") (pintype "bidirectional"))
    )
    (net (code "6") (name "A_XTAL2") (class "Default")
      (node (ref "C19") (pin "2") (pinfunction "2_2") (pintype "passive"))
      (node (ref "U$6") (pin "1") (pinfunction "1_1") (pintype "bidirectional"))
      (node (ref "U1") (pin "P$8") (pinfunction "XTAL2_P$8") (pintype "bidirectional"))
    )
    (net (code "7") (name "DJI_PPM") (class "Default")
      (node (ref "DJI_SIG") (pin "1") (pinfunction "1_1") (pintype "passive"))
      (node (ref "U$3") (pin "1") (pinfunction "PB6_1") (pintype "bidirectional"))
    )
    (net (code "8") (name "GND") (class "Default")
      (node (ref "ATOM_POW") (pin "P2") (pinfunction "N_P2") (pintype "bidirectional"))
      (node (ref "C1") (pin "2") (pinfunction "2_2") (pintype "passive"))
      (node (ref "C10") (pin "2") (pinfunction "2_2") (pintype "passive"))
      (node (ref "C12") (pin "2") (pinfunction "2_2") (pintype "passive"))
      (node (ref "C13") (pin "2") (pinfunction "2_2") (pintype "passive"))
      (node (ref "C14") (pin "2") (pinfunction "2_2") (pintype "passive"))
      (node (ref "C15") (pin "1") (pinfunction "1_1") (pintype "passive"))
      (node (ref "C16") (pin "2") (pinfunction "2_2") (pintype "passive"))
      (node (ref "C17") (pin "2") (pinfunction "2_2") (pintype "passive"))
      (node (ref "C18") (pin "2") (pinfunction "2_2") (pintype "passive"))
      (node (ref "C19") (pin "1") (pinfunction "1_1") (pintype "passive"))
      (node (ref "C2") (pin "2") (pinfunction "2_2") (pintype "passive"))
      (node (ref "C20") (pin "1") (pinfunction "1_1") (pintype "passive"))
      (node (ref "C21") (pin "2") (pinfunction "2_2") (pintype "passive"))
      (node (ref "C22") (pin "2") (pinfunction "2_2") (pintype "passive"))
      (node (ref "C23") (pin "2") (pinfunction "2_2") (pintype "passive"))
      (node (ref "C24") (pin "2") (pinfunction "2_2") (pintype "passive"))
      (node (ref "C26") (pin "2") (pinfunction "2_2") (pintype "passive"))
      (node (ref "C27") (pin "-") (pinfunction "-_-") (pintype "passive"))
      (node (ref "C29") (pin "2") (pinfunction "2_2") (pintype "passive"))
      (node (ref "C3") (pin "2") (pinfunction "2_2") (pintype "passive"))
      (node (ref "C30") (pin "2") (pinfunction "2_2") (pintype "passive"))
      (node (ref "C31") (pin "-") (pinfunction "-_-") (pintype "passive"))
      (node (ref "C4") (pin "2") (pinfunction "2_2") (pintype "passive"))
      (node (ref "C40") (pin "2") (pinfunction "2_2") (pintype "passive"))
      (node (ref "C41") (pin "2") (pinfunction "2_2") (pintype "passive"))
      (node (ref "C5") (pin "2") (pinfunction "2_2") (pintype "passive"))
      (node (ref "C6") (pin "2") (pinfunction "2_2") (pintype "passive"))
      (node (ref "C7") (pin "2") (pinfunction "2_2") (pintype "passive"))
      (node (ref "C8") (pin "2") (pinfunction "2_2") (pintype "passive"))
      (node (ref "C9") (pin "2") (pinfunction "2_2") (pintype "passive"))
      (node (ref "CONV") (pin "P$1") (pinfunction "EN_P$1") (pintype "input"))
      (node (ref "CONV") (pin "P$12") (pinfunction "FORCEON_P$12") (pintype "input"))
      (node (ref "CONV") (pin "P$14") (pinfunction "GND_P$14") (pintype "power_in"))
      (node (ref "DJI_POW") (pin "P2") (pinfunction "N_P2") (pintype "bidirectional"))
      (node (ref "DJI_SIG") (pin "3") (pinfunction "3_3") (pintype "passive"))
      (node (ref "I2C_1") (pin "4") (pinfunction "P$4_4") (pintype "bidirectional"))
      (node (ref "I2C_2") (pin "4") (pinfunction "P$4_4") (pintype "bidirectional"))
      (node (ref "J7") (pin "4") (pinfunction "P$4_4") (pintype "bidirectional"))
      (node (ref "KILL") (pin "GND") (pinfunction "GND_GND") (pintype "bidirectional"))
      (node (ref "KILL") (pin "GND2") (pinfunction "GND_GND2") (pintype "bidirectional"))
      (node (ref "LED1") (pin "C") (pinfunction "C_C") (pintype "passive"))
      (node (ref "MOUT0") (pin "P2") (pinfunction "N_P2") (pintype "bidirectional"))
      (node (ref "MOUT1") (pin "P2") (pinfunction "N_P2") (pintype "bidirectional"))
      (node (ref "MOUT2") (pin "P2") (pinfunction "N_P2") (pintype "bidirectional"))
      (node (ref "MOUT3") (pin "P2") (pinfunction "N_P2") (pintype "bidirectional"))
      (node (ref "Q1") (pin "2") (pinfunction "S_2") (pintype "passive"))
      (node (ref "Q10") (pin "2") (pinfunction "S_2") (pintype "passive"))
      (node (ref "Q11") (pin "2") (pinfunction "S_2") (pintype "passive"))
      (node (ref "Q12") (pin "2") (pinfunction "S_2") (pintype "passive"))
      (node (ref "Q13") (pin "2") (pinfunction "S_2") (pintype "passive"))
      (node (ref "Q14") (pin "2") (pinfunction "S_2") (pintype "passive"))
      (node (ref "Q2") (pin "2") (pinfunction "S_2") (pintype "passive"))
      (node (ref "Q3") (pin "2") (pinfunction "S_2") (pintype "passive"))
      (node (ref "Q4") (pin "2") (pinfunction "S_2") (pintype "passive"))
      (node (ref "Q6") (pin "2") (pinfunction "S_2") (pintype "passive"))
      (node (ref "Q7") (pin "2") (pinfunction "S_2") (pintype "passive"))
      (node (ref "Q8") (pin "2") (pinfunction "S_2") (pintype "passive"))
      (node (ref "Q9") (pin "2") (pinfunction "S_2") (pintype "passive"))
      (node (ref "R3") (pin "1") (pinfunction "1_1") (pintype "passive"))
      (node (ref "R7") (pin "1") (pinfunction "1_1") (pintype "passive"))
      (node (ref "R8") (pin "1") (pinfunction "1_1") (pintype "passive"))
      (node (ref "RC") (pin "GND") (pinfunction "GND_GND") (pintype "bidirectional"))
      (node (ref "RC") (pin "GND2") (pinfunction "GND_GND2") (pintype "bidirectional"))
      (node (ref "RSET") (pin "2") (pinfunction "2_2") (pintype "passive"))
      (node (ref "S1") (pin "P$1") (pinfunction "P$1_P$1") (pintype "bidirectional"))
      (node (ref "S2") (pin "P$1") (pinfunction "P$1_P$1") (pintype "bidirectional"))
      (node (ref "S3") (pin "P$1") (pinfunction "P$1_P$1") (pintype "bidirectional"))
      (node (ref "SV1") (pin "4") (pinfunction "GND_4") (pintype "passive"))
      (node (ref "S_R") (pin "S") (pinfunction "S_S") (pintype "passive"))
      (node (ref "S_R") (pin "S1") (pinfunction "S_S1") (pintype "passive"))
      (node (ref "U$1") (pin "2") (pinfunction "GND_2") (pintype "bidirectional"))
      (node (ref "U$1") (pin "4") (pinfunction "GND_4") (pintype "bidirectional"))
      (node (ref "U$2") (pin "3") (pinfunction "GND_3") (pintype "bidirectional"))
      (node (ref "U$2") (pin "9") (pinfunction "GND_9") (pintype "bidirectional"))
      (node (ref "U$3") (pin "12") (pinfunction "GND_12") (pintype "bidirectional"))
      (node (ref "U$3") (pin "27") (pinfunction "GND_27") (pintype "bidirectional"))
      (node (ref "U$3") (pin "3") (pinfunction "GNDA_3") (pintype "bidirectional"))
      (node (ref "U$3") (pin "32") (pinfunction "~{WAKE}_32") (pintype "bidirectional"))
      (node (ref "U$3") (pin "34") (pinfunction "XOSC0_34") (pintype "bidirectional"))
      (node (ref "U$3") (pin "35") (pinfunction "GNDX_35") (pintype "bidirectional"))
      (node (ref "U$3") (pin "39") (pinfunction "GND_39") (pintype "bidirectional"))
      (node (ref "U$3") (pin "55") (pinfunction "GND_55") (pintype "bidirectional"))
      (node (ref "U$4") (pin "P$6") (pinfunction "P$6_P$6") (pintype "bidirectional"))
      (node (ref "U$5") (pin "1") (pinfunction "GND_1") (pintype "power_in"))
      (node (ref "U$5") (pin "7") (pinfunction "GND_7") (pintype "power_in"))
      (node (ref "U$6") (pin "2") (pinfunction "GND_2") (pintype "bidirectional"))
      (node (ref "U$6") (pin "4") (pinfunction "GND_4") (pintype "bidirectional"))
      (node (ref "U1") (pin "P$21") (pinfunction "AGND_P$21") (pintype "bidirectional"))
      (node (ref "U1") (pin "P$3") (pinfunction "GND_P$3") (pintype "bidirectional"))
      (node (ref "U1") (pin "P$5") (pinfunction "GND2_P$5") (pintype "bidirectional"))
      (node (ref "U3") (pin "2") (pinfunction "GND_2") (pintype "power_in"))
      (node (ref "V_BATT1") (pin "GND-1") (pinfunction "GND_GND-1") (pintype "bidirectional"))
      (node (ref "V_BATT1") (pin "GND-2") (pinfunction "GND_GND-2") (pintype "bidirectional"))
    )
    (net (code "9") (name "ICDI_TCK") (class "Default")
      (node (ref "R12") (pin "1") (pinfunction "1_1") (pintype "passive"))
      (node (ref "U$2") (pin "4") (pinfunction "TCK_4") (pintype "bidirectional"))
      (node (ref "U$3") (pin "52") (pinfunction "PC0/TCK/SWCLK_52") (pintype "bidirectional"))
    )
    (net (code "10") (name "ICDI_TDI") (class "Default")
      (node (ref "U$2") (pin "8") (pinfunction "TDI_8") (pintype "bidirectional"))
      (node (ref "U$3") (pin "50") (pinfunction "PC2/TDI_50") (pintype "bidirectional"))
    )
    (net (code "11") (name "ICDI_TDO") (class "Default")
      (node (ref "U$2") (pin "6") (pinfunction "TDO_6") (pintype "bidirectional"))
      (node (ref "U$3") (pin "49") (pinfunction "PC3/TDO/SWO_49") (pintype "bidirectional"))
    )
    (net (code "12") (name "ICDI_TMS") (class "Default")
      (node (ref "R15") (pin "1") (pinfunction "1_1") (pintype "passive"))
      (node (ref "U$2") (pin "2") (pinfunction "TMS_2") (pintype "bidirectional"))
      (node (ref "U$3") (pin "51") (pinfunction "PC1/TMS/SWDIO_51") (pintype "bidirectional"))
    )
    (net (code "13") (name "KILL_1") (class "Default")
      (node (ref "KILL") (pin "P$1") (pinfunction "P$1_P$1") (pintype "bidirectional"))
      (node (ref "U$3") (pin "59") (pinfunction "PE4_59") (pintype "bidirectional"))
    )
    (net (code "14") (name "KILL_2") (class "Default")
      (node (ref "KILL") (pin "P$2") (pinfunction "P$2_P$2") (pintype "bidirectional"))
      (node (ref "U$3") (pin "60") (pinfunction "PE5_60") (pintype "bidirectional"))
    )
    (net (code "15") (name "KILL_4") (class "Default")
      (node (ref "KILL") (pin "P$4") (pinfunction "P$4_P$4") (pintype "bidirectional"))
      (node (ref "U$3") (pin "7") (pinfunction "PE2_7") (pintype "bidirectional"))
    )
    (net (code "16") (name "KILL_5") (class "Default")
      (node (ref "KILL") (pin "P$5") (pinfunction "P$5_P$5") (pintype "bidirectional"))
      (node (ref "U$3") (pin "8") (pinfunction "PE1_8") (pintype "bidirectional"))
      (node (ref "U1") (pin "P$24") (pinfunction "(ADC1)PC1_P$24") (pintype "bidirectional"))
    )
    (net (code "17") (name "KILL_6") (class "Default")
      (node (ref "KILL") (pin "P$6") (pinfunction "P$6_P$6") (pintype "bidirectional"))
      (node (ref "U$3") (pin "9") (pinfunction "PE0_9") (pintype "bidirectional"))
    )
    (net (code "18") (name "KILL_SIG") (class "Default")
      (node (ref "KILL") (pin "P$3") (pinfunction "P$3_P$3") (pintype "bidirectional"))
      (node (ref "U$3") (pin "6") (pinfunction "PE3_6") (pintype "bidirectional"))
      (node (ref "U1") (pin "P$23") (pinfunction "(ADC0)PC0_P$23") (pintype "bidirectional"))
    )
    (net (code "19") (name "LED1") (class "Default")
      (node (ref "Q8") (pin "1") (pinfunction "G_1") (pintype "passive"))
      (node (ref "U1") (pin "P$12") (pinfunction "(ICP)PB0_P$12") (pintype "bidirectional"))
    )
    (net (code "20") (name "LED2") (class "Default")
      (node (ref "Q7") (pin "1") (pinfunction "G_1") (pintype "passive"))
      (node (ref "U1") (pin "P$13") (pinfunction "(OC1)PB1_P$13") (pintype "bidirectional"))
    )
    (net (code "21") (name "LED3") (class "Default")
      (node (ref "Q6") (pin "1") (pinfunction "G_1") (pintype "passive"))
      (node (ref "U1") (pin "P$2") (pinfunction "(T0)PD4_P$2") (pintype "bidirectional"))
    )
    (net (code "22") (name "MISO") (class "Default")
      (node (ref "SV1") (pin "1") (pinfunction "MISO_1") (pintype "passive"))
      (node (ref "U1") (pin "P$16") (pinfunction "(MISO)PB4_P$16") (pintype "bidirectional"))
    )
    (net (code "23") (name "MOSI") (class "Default")
      (node (ref "SV1") (pin "5") (pinfunction "MOSI_5") (pintype "passive"))
      (node (ref "U1") (pin "P$15") (pinfunction "(MOSI)PB3_P$15") (pintype "bidirectional"))
    )
    (net (code "24") (name "MOTOR_LOGIC") (class "Default")
      (node (ref "Q1") (pin "1") (pinfunction "G_1") (pintype "passive"))
      (node (ref "R3") (pin "2") (pinfunction "2_2") (pintype "passive"))
      (node (ref "U1") (pin "P$11") (pinfunction "(AIN1)PD7_P$11") (pintype "bidirectional"))
    )
    (net (code "25") (name "M_ENABLE") (class "Default")
      (node (ref "Q21") (pin "G") (pinfunction "G_G") (pintype "passive"))
      (node (ref "Q22") (pin "G") (pinfunction "G_G") (pintype "passive"))
      (node (ref "Q23") (pin "G") (pinfunction "G_G") (pintype "passive"))
      (node (ref "Q24") (pin "G") (pinfunction "G_G") (pintype "passive"))
      (node (ref "Q5") (pin "G") (pinfunction "G_G") (pintype "passive"))
      (node (ref "R1") (pin "1") (pinfunction "1_1") (pintype "passive"))
      (node (ref "U$4") (pin "P$2") (pinfunction "P$2_P$2") (pintype "bidirectional"))
    )
    (net (code "26") (name "M_EN_PRE") (class "Default")
      (node (ref "R2") (pin "2") (pinfunction "2_2") (pintype "passive"))
      (node (ref "U$4") (pin "P$1") (pinfunction "P$1_P$1") (pintype "bidirectional"))
    )
    (net (code "27") (name "Net-(CONV-C1+)") (class "Default")
      (node (ref "C37") (pin "1") (pinfunction "1_1") (pintype "passive"))
      (node (ref "CONV") (pin "P$2") (pinfunction "C1+_P$2") (pintype "passive"))
    )
    (net (code "28") (name "Net-(CONV-C1-)") (class "Default")
      (node (ref "C37") (pin "2") (pinfunction "2_2") (pintype "passive"))
      (node (ref "CONV") (pin "P$4") (pinfunction "C1-_P$4") (pintype "passive"))
    )
    (net (code "29") (name "Net-(CONV-C2+)") (class "Default")
      (node (ref "C38") (pin "1") (pinfunction "1_1") (pintype "passive"))
      (node (ref "CONV") (pin "P$5") (pinfunction "C2+_P$5") (pintype "passive"))
    )
    (net (code "30") (name "Net-(CONV-C2-)") (class "Default")
      (node (ref "C38") (pin "2") (pinfunction "2_2") (pintype "passive"))
      (node (ref "CONV") (pin "P$6") (pinfunction "C2-_P$6") (pintype "passive"))
    )
    (net (code "31") (name "Net-(CONV-V+)") (class "Default")
      (node (ref "C39") (pin "1") (pinfunction "1_1") (pintype "passive"))
      (node (ref "CONV") (pin "P$3") (pinfunction "V+_P$3") (pintype "passive"))
    )
    (net (code "32") (name "Net-(CONV-V-)") (class "Default")
      (node (ref "C40") (pin "1") (pinfunction "1_1") (pintype "passive"))
      (node (ref "CONV") (pin "P$7") (pinfunction "V-_P$7") (pintype "passive"))
    )
    (net (code "33") (name "Net-(D1-B)") (class "Default")
      (node (ref "D1") (pin "4") (pinfunction "B_4") (pintype "passive"))
      (node (ref "R6") (pin "2") (pinfunction "2_2") (pintype "passive"))
    )
    (net (code "34") (name "Net-(D1-G)") (class "Default")
      (node (ref "D1") (pin "3") (pinfunction "G_3") (pintype "passive"))
      (node (ref "R5") (pin "2") (pinfunction "2_2") (pintype "passive"))
    )
    (net (code "35") (name "Net-(D1-R)") (class "Default")
      (node (ref "D1") (pin "2") (pinfunction "R_2") (pintype "passive"))
      (node (ref "R4") (pin "2") (pinfunction "2_2") (pintype "passive"))
    )
    (net (code "36") (name "Net-(D2-B)") (class "Default")
      (node (ref "D2") (pin "4") (pinfunction "B_4") (pintype "passive"))
      (node (ref "R14") (pin "2") (pinfunction "2_2") (pintype "passive"))
    )
    (net (code "37") (name "Net-(D2-G)") (class "Default")
      (node (ref "D2") (pin "3") (pinfunction "G_3") (pintype "passive"))
      (node (ref "R13") (pin "2") (pinfunction "2_2") (pintype "passive"))
    )
    (net (code "38") (name "Net-(D2-R)") (class "Default")
      (node (ref "D2") (pin "2") (pinfunction "R_2") (pintype "passive"))
      (node (ref "R10") (pin "2") (pinfunction "2_2") (pintype "passive"))
    )
    (net (code "39") (name "Net-(DJI_POW-P)") (class "Default")
      (node (ref "DJI_POW") (pin "P1") (pinfunction "P_P1") (pintype "bidirectional"))
      (node (ref "Q5") (pin "D1") (pinfunction "D1_D1") (pintype "passive"))
      (node (ref "Q5") (pin "D2") (pinfunction "D1_D2") (pintype "passive"))
      (node (ref "Q5") (pin "D3") (pinfunction "D1_D3") (pintype "passive"))
      (node (ref "Q5") (pin "D4") (pinfunction "D1_D4") (pintype "passive"))
      (node (ref "Q5") (pin "D5") (pinfunction "D1_D5") (pintype "passive"))
    )
    (net (code "40") (name "Net-(LED1-PadA)") (class "Default")
      (node (ref "LED1") (pin "A") (pinfunction "A_A") (pintype "passive"))
      (node (ref "R16") (pin "1") (pinfunction "1_1") (pintype "passive"))
    )
    (net (code "41") (name "Net-(MOUT0-P)") (class "Default")
      (node (ref "MOUT0") (pin "P1") (pinfunction "P_P1") (pintype "bidirectional"))
      (node (ref "Q21") (pin "D1") (pinfunction "D1_D1") (pintype "passive"))
      (node (ref "Q21") (pin "D2") (pinfunction "D1_D2") (pintype "passive"))
      (node (ref "Q21") (pin "D3") (pinfunction "D1_D3") (pintype "passive"))
      (node (ref "Q21") (pin "D4") (pinfunction "D1_D4") (pintype "passive"))
      (node (ref "Q21") (pin "D5") (pinfunction "D1_D5") (pintype "passive"))
    )
    (net (code "42") (name "Net-(MOUT1-P)") (class "Default")
      (node (ref "MOUT1") (pin "P1") (pinfunction "P_P1") (pintype "bidirectional"))
      (node (ref "Q24") (pin "D1") (pinfunction "D1_D1") (pintype "passive"))
      (node (ref "Q24") (pin "D2") (pinfunction "D1_D2") (pintype "passive"))
      (node (ref "Q24") (pin "D3") (pinfunction "D1_D3") (pintype "passive"))
      (node (ref "Q24") (pin "D4") (pinfunction "D1_D4") (pintype "passive"))
      (node (ref "Q24") (pin "D5") (pinfunction "D1_D5") (pintype "passive"))
    )
    (net (code "43") (name "Net-(MOUT2-P)") (class "Default")
      (node (ref "MOUT2") (pin "P1") (pinfunction "P_P1") (pintype "bidirectional"))
      (node (ref "Q22") (pin "D1") (pinfunction "D1_D1") (pintype "passive"))
      (node (ref "Q22") (pin "D2") (pinfunction "D1_D2") (pintype "passive"))
      (node (ref "Q22") (pin "D3") (pinfunction "D1_D3") (pintype "passive"))
      (node (ref "Q22") (pin "D4") (pinfunction "D1_D4") (pintype "passive"))
      (node (ref "Q22") (pin "D5") (pinfunction "D1_D5") (pintype "passive"))
    )
    (net (code "44") (name "Net-(MOUT3-P)") (class "Default")
      (node (ref "MOUT3") (pin "P1") (pinfunction "P_P1") (pintype "bidirectional"))
      (node (ref "Q23") (pin "D1") (pinfunction "D1_D1") (pintype "passive"))
      (node (ref "Q23") (pin "D2") (pinfunction "D1_D2") (pintype "passive"))
      (node (ref "Q23") (pin "D3") (pinfunction "D1_D3") (pintype "passive"))
      (node (ref "Q23") (pin "D4") (pinfunction "D1_D4") (pintype "passive"))
      (node (ref "Q23") (pin "D5") (pinfunction "D1_D5") (pintype "passive"))
    )
    (net (code "45") (name "Net-(Q1-D)") (class "Default")
      (node (ref "Q1") (pin "3") (pinfunction "D_3") (pintype "passive"))
      (node (ref "R2") (pin "1") (pinfunction "1_1") (pintype "passive"))
    )
    (net (code "46") (name "Net-(Q2-D)") (class "Default")
      (node (ref "Q2") (pin "3") (pinfunction "D_3") (pintype "passive"))
      (node (ref "R6") (pin "1") (pinfunction "1_1") (pintype "passive"))
    )
    (net (code "47") (name "Net-(Q3-D)") (class "Default")
      (node (ref "Q3") (pin "3") (pinfunction "D_3") (pintype "passive"))
      (node (ref "R5") (pin "1") (pinfunction "1_1") (pintype "passive"))
    )
    (net (code "48") (name "Net-(Q4-D)") (class "Default")
      (node (ref "Q4") (pin "3") (pinfunction "D_3") (pintype "passive"))
      (node (ref "R4") (pin "1") (pinfunction "1_1") (pintype "passive"))
    )
    (net (code "49") (name "Net-(Q6-D)") (class "Default")
      (node (ref "Q6") (pin "3") (pinfunction "D_3") (pintype "passive"))
      (node (ref "R14") (pin "1") (pinfunction "1_1") (pintype "passive"))
    )
    (net (code "50") (name "Net-(Q7-D)") (class "Default")
      (node (ref "Q7") (pin "3") (pinfunction "D_3") (pintype "passive"))
      (node (ref "R13") (pin "1") (pinfunction "1_1") (pintype "passive"))
    )
    (net (code "51") (name "Net-(Q8-D)") (class "Default")
      (node (ref "Q8") (pin "3") (pinfunction "D_3") (pintype "passive"))
      (node (ref "R10") (pin "1") (pinfunction "1_1") (pintype "passive"))
    )
    (net (code "52") (name "Net-(Q9-D)") (class "Default")
      (node (ref "Q9") (pin "3") (pinfunction "D_3") (pintype "passive"))
      (node (ref "R18") (pin "1") (pinfunction "1_1") (pintype "passive"))
    )
    (net (code "53") (name "Net-(Q10-D)") (class "Default")
      (node (ref "Q10") (pin "3") (pinfunction "D_3") (pintype "passive"))
      (node (ref "Q9") (pin "1") (pinfunction "G_1") (pintype "passive"))
      (node (ref "R17") (pin "1") (pinfunction "1_1") (pintype "passive"))
    )
    (net (code "54") (name "Net-(Q11-D)") (class "Default")
      (node (ref "Q11") (pin "3") (pinfunction "D_3") (pintype "passive"))
      (node (ref "R20") (pin "1") (pinfunction "1_1") (pintype "passive"))
    )
    (net (code "55") (name "Net-(Q11-G)") (class "Default")
      (node (ref "Q11") (pin "1") (pinfunction "G_1") (pintype "passive"))
      (node (ref "Q12") (pin "3") (pinfunction "D_3") (pintype "passive"))
      (node (ref "R19") (pin "1") (pinfunction "1_1") (pintype "passive"))
    )
    (net (code "56") (name "Net-(Q13-D)") (class "Default")
      (node (ref "Q13") (pin "3") (pinfunction "D_3") (pintype "passive"))
      (node (ref "R24") (pin "1") (pinfunction "1_1") (pintype "passive"))
    )
    (net (code "57") (name "Net-(Q13-G)") (class "Default")
      (node (ref "Q13") (pin "1") (pinfunction "G_1") (pintype "passive"))
      (node (ref "Q14") (pin "3") (pinfunction "D_3") (pintype "passive"))
      (node (ref "R22") (pin "1") (pinfunction "1_1") (pintype "passive"))
    )
    (net (code "58") (name "Net-(R11-Pad1)") (class "Default")
      (node (ref "R11") (pin "1") (pinfunction "1_1") (pintype "passive"))
      (node (ref "S_R") (pin "P") (pinfunction "P_P") (pintype "passive"))
      (node (ref "S_R") (pin "P1") (pinfunction "P_P1") (pintype "passive"))
    )
    (net (code "59") (name "Net-(R17-Pad2)") (class "Default")
      (node (ref "R17") (pin "2") (pinfunction "2_2") (pintype "passive"))
      (node (ref "S1") (pin "P$6") (pinfunction "P$6_P$6") (pintype "bidirectional"))
    )
    (net (code "60") (name "Net-(R18-Pad2)") (class "Default")
      (node (ref "R18") (pin "2") (pinfunction "2_2") (pintype "passive"))
      (node (ref "S1") (pin "P$4") (pinfunction "P$4_P$4") (pintype "bidirectional"))
    )
    (net (code "61") (name "Net-(R19-Pad2)") (class "Default")
      (node (ref "R19") (pin "2") (pinfunction "2_2") (pintype "passive"))
      (node (ref "S2") (pin "P$6") (pinfunction "P$6_P$6") (pintype "bidirectional"))
    )
    (net (code "62") (name "Net-(R20-Pad2)") (class "Default")
      (node (ref "R20") (pin "2") (pinfunction "2_2") (pintype "passive"))
      (node (ref "S2") (pin "P$4") (pinfunction "P$4_P$4") (pintype "bidirectional"))
    )
    (net (code "63") (name "Net-(R21-Pad2)") (class "Default")
      (node (ref "R21") (pin "2") (pinfunction "2_2") (pintype "passive"))
      (node (ref "S2") (pin "P$2") (pinfunction "P$2_P$2") (pintype "bidirectional"))
    )
    (net (code "64") (name "Net-(R22-Pad2)") (class "Default")
      (node (ref "R22") (pin "2") (pinfunction "2_2") (pintype "passive"))
      (node (ref "S3") (pin "P$6") (pinfunction "P$6_P$6") (pintype "bidirectional"))
    )
    (net (code "65") (name "Net-(R23-Pad2)") (class "Default")
      (node (ref "R23") (pin "2") (pinfunction "2_2") (pintype "passive"))
      (node (ref "S1") (pin "P$2") (pinfunction "P$2_P$2") (pintype "bidirectional"))
    )
    (net (code "66") (name "Net-(R24-Pad2)") (class "Default")
      (node (ref "R24") (pin "2") (pinfunction "2_2") (pintype "passive"))
      (node (ref "S3") (pin "P$4") (pinfunction "P$4_P$4") (pintype "bidirectional"))
    )
    (net (code "67") (name "Net-(R25-Pad2)") (class "Default")
      (node (ref "R25") (pin "2") (pinfunction "2_2") (pintype "passive"))
      (node (ref "S3") (pin "P$2") (pinfunction "P$2_P$2") (pintype "bidirectional"))
    )
    (net (code "68") (name "Net-(U$5-ADJ)") (class "Default")
      (node (ref "RSET") (pin "1") (pinfunction "1_1") (pintype "passive"))
      (node (ref "U$5") (pin "4") (pinfunction "ADJ_4") (pintype "passive"))
    )
    (net (code "69") (name "OPT_SWITCH_1") (class "Default")
      (node (ref "Q10") (pin "1") (pinfunction "G_1") (pintype "passive"))
      (node (ref "R23") (pin "1") (pinfunction "1_1") (pintype "passive"))
      (node (ref "U$3") (pin "46") (pinfunction "PB1/USB0VBUS_46") (pintype "bidirectional"))
    )
    (net (code "70") (name "OPT_SWITCH_2") (class "Default")
      (node (ref "Q12") (pin "1") (pinfunction "G_1") (pintype "passive"))
      (node (ref "R21") (pin "1") (pinfunction "1_1") (pintype "passive"))
      (node (ref "U$3") (pin "47") (pinfunction "PB2/I2C0SCL_47") (pintype "bidirectional"))
    )
    (net (code "71") (name "OPT_SWITCH_3") (class "Default")
      (node (ref "Q14") (pin "1") (pinfunction "G_1") (pintype "passive"))
      (node (ref "R25") (pin "1") (pinfunction "1_1") (pintype "passive"))
      (node (ref "U$3") (pin "48") (pinfunction "PB3/I2C0SDA_48") (pintype "bidirectional"))
    )
    (net (code "72") (name "RC_1") (class "Default")
      (node (ref "RC") (pin "P$1") (pinfunction "P$1_P$1") (pintype "bidirectional"))
      (node (ref "U$3") (pin "19") (pinfunction "PA2/SSI0CLK_19") (pintype "bidirectional"))
    )
    (net (code "73") (name "RC_2") (class "Default")
      (node (ref "RC") (pin "P$2") (pinfunction "P$2_P$2") (pintype "bidirectional"))
      (node (ref "U$3") (pin "20") (pinfunction "PA3/SSI0FSS_20") (pintype "bidirectional"))
    )
    (net (code "74") (name "RC_3") (class "Default")
      (node (ref "RC") (pin "P$3") (pinfunction "P$3_P$3") (pintype "bidirectional"))
      (node (ref "U$3") (pin "21") (pinfunction "PA4/SSI0RX_21") (pintype "bidirectional"))
    )
    (net (code "75") (name "RC_4") (class "Default")
      (node (ref "RC") (pin "P$4") (pinfunction "P$4_P$4") (pintype "bidirectional"))
      (node (ref "U$3") (pin "22") (pinfunction "PA5/SSI0TX_22") (pintype "bidirectional"))
    )
    (net (code "76") (name "RC_5") (class "Default")
      (node (ref "RC") (pin "P$5") (pinfunction "P$5_P$5") (pintype "bidirectional"))
      (node (ref "U$3") (pin "23") (pinfunction "PA6_23") (pintype "bidirectional"))
    )
    (net (code "77") (name "RC_6") (class "Default")
      (node (ref "RC") (pin "P$6") (pinfunction "P$6_P$6") (pintype "bidirectional"))
      (node (ref "U$3") (pin "24") (pinfunction "PA7_24") (pintype "bidirectional"))
    )
    (net (code "78") (name "RESET") (class "Default")
      (node (ref "C10") (pin "1") (pinfunction "1_1") (pintype "passive"))
      (node (ref "C4") (pin "1") (pinfunction "1_1") (pintype "passive"))
      (node (ref "R11") (pin "2") (pinfunction "2_2") (pintype "passive"))
      (node (ref "R9") (pin "1") (pinfunction "1_1") (pintype "passive"))
      (node (ref "SV1") (pin "3") (pinfunction "RESET_3") (pintype "passive"))
      (node (ref "U$2") (pin "10") (pinfunction "RESET_10") (pintype "bidirectional"))
      (node (ref "U$3") (pin "38") (pinfunction "~{RST}_38") (pintype "bidirectional"))
      (node (ref "U1") (pin "P$29") (pinfunction "RESET_P$29") (pintype "bidirectional"))
    )
    (net (code "79") (name "RS-232_RX1") (class "Default")
      (node (ref "CONV") (pin "P$8") (pinfunction "RIN_P$8") (pintype "input"))
      (node (ref "J7") (pin "3") (pinfunction "P$3_3") (pintype "bidirectional"))
    )
    (net (code "80") (name "RS-232_TX1") (class "Default")
      (node (ref "CONV") (pin "P$13") (pinfunction "DOUT_P$13") (pintype "output"))
      (node (ref "J7") (pin "2") (pinfunction "P$2_2") (pintype "bidirectional"))
    )
    (net (code "81") (name "RX1_3V3") (class "Default")
      (node (ref "CONV") (pin "P$9") (pinfunction "ROUT_P$9") (pintype "output"))
      (node (ref "U$3") (pin "17") (pinfunction "PA0/U0RX_17") (pintype "bidirectional"))
    )
    (net (code "82") (name "SCK") (class "Default")
      (node (ref "SV1") (pin "2") (pinfunction "SCK_2") (pintype "passive"))
      (node (ref "U1") (pin "P$17") (pinfunction "(SCK)PB5_P$17") (pintype "bidirectional"))
    )
    (net (code "83") (name "SCL_3V3") (class "Default")
      (node (ref "I2C_1") (pin "2") (pinfunction "P$2_2") (pintype "bidirectional"))
      (node (ref "I2C_2") (pin "2") (pinfunction "P$2_2") (pintype "bidirectional"))
      (node (ref "R8") (pin "2") (pinfunction "2_2") (pintype "passive"))
      (node (ref "U$3") (pin "61") (pinfunction "PD0_61") (pintype "bidirectional"))
      (node (ref "U1") (pin "P$28") (pinfunction "(ADC5)PC5_P$28") (pintype "bidirectional"))
    )
    (net (code "84") (name "SDA_3V3") (class "Default")
      (node (ref "I2C_1") (pin "3") (pinfunction "P$3_3") (pintype "bidirectional"))
      (node (ref "I2C_2") (pin "3") (pinfunction "P$3_3") (pintype "bidirectional"))
      (node (ref "R7") (pin "2") (pinfunction "2_2") (pintype "passive"))
      (node (ref "U$3") (pin "62") (pinfunction "PD1_62") (pintype "bidirectional"))
      (node (ref "U1") (pin "P$27") (pinfunction "(ADC4)PC4_P$27") (pintype "bidirectional"))
    )
    (net (code "85") (name "TX1_3V3") (class "Default")
      (node (ref "CONV") (pin "P$11") (pinfunction "DIN_P$11") (pintype "input"))
      (node (ref "U$3") (pin "18") (pinfunction "PA1/U0TX_18") (pintype "bidirectional"))
    )
    (net (code "86") (name "T_BLUE_LED") (class "Default")
      (node (ref "Q2") (pin "1") (pinfunction "G_1") (pintype "passive"))
      (node (ref "U$3") (pin "30") (pinfunction "PF2_30") (pintype "bidirectional"))
    )
    (net (code "87") (name "T_GREEN_LED") (class "Default")
      (node (ref "Q3") (pin "1") (pinfunction "G_1") (pintype "passive"))
      (node (ref "U$3") (pin "31") (pinfunction "PF3_31") (pintype "bidirectional"))
    )
    (net (code "88") (name "T_OSC0") (class "Default")
      (node (ref "C18") (pin "1") (pinfunction "1_1") (pintype "passive"))
      (node (ref "U$1") (pin "3") (pinfunction "2_3") (pintype "bidirectional"))
      (node (ref "U$3") (pin "40") (pinfunction "OSC0_40") (pintype "bidirectional"))
    )
    (net (code "89") (name "T_OSC1") (class "Default")
      (node (ref "C17") (pin "1") (pinfunction "1_1") (pintype "passive"))
      (node (ref "U$1") (pin "1") (pinfunction "1_1") (pintype "bidirectional"))
      (node (ref "U$3") (pin "41") (pinfunction "OSC1_41") (pintype "bidirectional"))
    )
    (net (code "90") (name "T_RED_LED") (class "Default")
      (node (ref "Q4") (pin "1") (pinfunction "G_1") (pintype "passive"))
      (node (ref "U$3") (pin "29") (pinfunction "PF1_29") (pintype "bidirectional"))
    )
    (net (code "91") (name "T_VDDC") (class "Default")
      (node (ref "C1") (pin "1") (pinfunction "1_1") (pintype "passive"))
      (node (ref "C12") (pin "1") (pinfunction "1_1") (pintype "passive"))
      (node (ref "C13") (pin "1") (pinfunction "1_1") (pintype "passive"))
      (node (ref "C14") (pin "1") (pinfunction "1_1") (pintype "passive"))
      (node (ref "U$3") (pin "25") (pinfunction "VDDC_25") (pintype "bidirectional"))
      (node (ref "U$3") (pin "56") (pinfunction "VDDC_56") (pintype "bidirectional"))
    )
    (net (code "92") (name "V_BATT") (class "Default")
      (node (ref "C26") (pin "1") (pinfunction "1_1") (pintype "passive"))
      (node (ref "C3") (pin "1") (pinfunction "1_1") (pintype "passive"))
      (node (ref "C31") (pin "+") (pinfunction "+_+") (pintype "passive"))
      (node (ref "Q21") (pin "S1") (pinfunction "S1_S1") (pintype "passive"))
      (node (ref "Q21") (pin "S2") (pinfunction "S1_S2") (pintype "passive"))
      (node (ref "Q21") (pin "S3") (pinfunction "S1_S3") (pintype "passive"))
      (node (ref "Q22") (pin "S1") (pinfunction "S1_S1") (pintype "passive"))
      (node (ref "Q22") (pin "S2") (pinfunction "S1_S2") (pintype "passive"))
      (node (ref "Q22") (pin "S3") (pinfunction "S1_S3") (pintype "passive"))
      (node (ref "Q23") (pin "S1") (pinfunction "S1_S1") (pintype "passive"))
      (node (ref "Q23") (pin "S2") (pinfunction "S1_S2") (pintype "passive"))
      (node (ref "Q23") (pin "S3") (pinfunction "S1_S3") (pintype "passive"))
      (node (ref "Q24") (pin "S1") (pinfunction "S1_S1") (pintype "passive"))
      (node (ref "Q24") (pin "S2") (pinfunction "S1_S2") (pintype "passive"))
      (node (ref "Q24") (pin "S3") (pinfunction "S1_S3") (pintype "passive"))
      (node (ref "Q5") (pin "S1") (pinfunction "S1_S1") (pintype "passive"))
      (node (ref "Q5") (pin "S2") (pinfunction "S1_S2") (pintype "passive"))
      (node (ref "Q5") (pin "S3") (pinfunction "S1_S3") (pintype "passive"))
      (node (ref "R1") (pin "2") (pinfunction "2_2") (pintype "passive"))
      (node (ref "U$5") (pin "2") (pinfunction "V_I_2") (pintype "input"))
      (node (ref "V_BATT1") (pin "VCC-1") (pinfunction "VCC_VCC-1") (pintype "bidirectional"))
      (node (ref "V_BATT1") (pin "VCC-2") (pinfunction "VCC_VCC-2") (pintype "bidirectional"))
    )
    (net (code "93") (name "unconnected-(CONV-INVLAID-PadP$10)") (class "Default")
      (node (ref "CONV") (pin "P$10") (pinfunction "INVLAID_P$10") (pintype "output"))
    )
    (net (code "94") (name "unconnected-(S1-PadP$3)") (class "Default")
      (node (ref "S1") (pin "P$3") (pinfunction "P$3_P$3") (pintype "bidirectional"))
    )
    (net (code "95") (name "unconnected-(S2-PadP$3)") (class "Default")
      (node (ref "S2") (pin "P$3") (pinfunction "P$3_P$3") (pintype "bidirectional"))
    )
    (net (code "96") (name "unconnected-(S3-PadP$3)") (class "Default")
      (node (ref "S3") (pin "P$3") (pinfunction "P$3_P$3") (pintype "bidirectional"))
    )
    (net (code "97") (name "unconnected-(U$2-VCC-Pad1)") (class "Default")
      (node (ref "U$2") (pin "1") (pinfunction "VCC_1") (pintype "bidirectional"))
    )
    (net (code "98") (name "unconnected-(U$3-PB0{slash}USB0ID-Pad45)") (class "Default")
      (node (ref "U$3") (pin "45") (pinfunction "PB0/USB0ID_45") (pintype "bidirectional"))
    )
    (net (code "99") (name "unconnected-(U$3-PB4-Pad58)") (class "Default")
      (node (ref "U$3") (pin "58") (pinfunction "PB4_58") (pintype "bidirectional"))
    )
    (net (code "100") (name "unconnected-(U$3-PB5-Pad57)") (class "Default")
      (node (ref "U$3") (pin "57") (pinfunction "PB5_57") (pintype "bidirectional"))
    )
    (net (code "101") (name "unconnected-(U$3-PB7-Pad4)") (class "Default")
      (node (ref "U$3") (pin "4") (pinfunction "PB7_4") (pintype "bidirectional"))
    )
    (net (code "102") (name "unconnected-(U$3-PC4-Pad16)") (class "Default")
      (node (ref "U$3") (pin "16") (pinfunction "PC4_16") (pintype "bidirectional"))
    )
    (net (code "103") (name "unconnected-(U$3-PC5-Pad15)") (class "Default")
      (node (ref "U$3") (pin "15") (pinfunction "PC5_15") (pintype "bidirectional"))
    )
    (net (code "104") (name "unconnected-(U$3-PC6-Pad14)") (class "Default")
      (node (ref "U$3") (pin "14") (pinfunction "PC6_14") (pintype "bidirectional"))
    )
    (net (code "105") (name "unconnected-(U$3-PC7-Pad13)") (class "Default")
      (node (ref "U$3") (pin "13") (pinfunction "PC7_13") (pintype "bidirectional"))
    )
    (net (code "106") (name "unconnected-(U$3-PD2-Pad63)") (class "Default")
      (node (ref "U$3") (pin "63") (pinfunction "PD2_63") (pintype "bidirectional"))
    )
    (net (code "107") (name "unconnected-(U$3-PD3-Pad64)") (class "Default")
      (node (ref "U$3") (pin "64") (pinfunction "PD3_64") (pintype "bidirectional"))
    )
    (net (code "108") (name "unconnected-(U$3-PD4-Pad43)") (class "Default")
      (node (ref "U$3") (pin "43") (pinfunction "PD4_43") (pintype "bidirectional"))
    )
    (net (code "109") (name "unconnected-(U$3-PD5-Pad44)") (class "Default")
      (node (ref "U$3") (pin "44") (pinfunction "PD5_44") (pintype "bidirectional"))
    )
    (net (code "110") (name "unconnected-(U$3-PD6-Pad53)") (class "Default")
      (node (ref "U$3") (pin "53") (pinfunction "PD6_53") (pintype "bidirectional"))
    )
    (net (code "111") (name "unconnected-(U$3-PD7-Pad10)") (class "Default")
      (node (ref "U$3") (pin "10") (pinfunction "PD7_10") (pintype "bidirectional"))
    )
    (net (code "112") (name "unconnected-(U$3-PF0-Pad28)") (class "Default")
      (node (ref "U$3") (pin "28") (pinfunction "PF0_28") (pintype "bidirectional"))
    )
    (net (code "113") (name "unconnected-(U$3-PF4-Pad5)") (class "Default")
      (node (ref "U$3") (pin "5") (pinfunction "PF4_5") (pintype "bidirectional"))
    )
    (net (code "114") (name "unconnected-(U$3-XOSC1-Pad36)") (class "Default")
      (node (ref "U$3") (pin "36") (pinfunction "XOSC1_36") (pintype "bidirectional"))
    )
    (net (code "115") (name "unconnected-(U$3-~{HIB}-Pad33)") (class "Default")
      (node (ref "U$3") (pin "33") (pinfunction "~{HIB}_33") (pintype "bidirectional"))
    )
    (net (code "116") (name "unconnected-(U$4-PadP$3)") (class "Default")
      (node (ref "U$4") (pin "P$3") (pinfunction "P$3_P$3") (pintype "bidirectional"))
    )
    (net (code "117") (name "unconnected-(U$4-PadP$4)") (class "Default")
      (node (ref "U$4") (pin "P$4") (pinfunction "P$4_P$4") (pintype "bidirectional"))
    )
    (net (code "118") (name "unconnected-(U1-(ADC2)PC2-PadP$25)") (class "Default")
      (node (ref "U1") (pin "P$25") (pinfunction "(ADC2)PC2_P$25") (pintype "bidirectional"))
    )
    (net (code "119") (name "unconnected-(U1-(ADC3)PC3-PadP$26)") (class "Default")
      (node (ref "U1") (pin "P$26") (pinfunction "(ADC3)PC3_P$26") (pintype "bidirectional"))
    )
    (net (code "120") (name "unconnected-(U1-(AIN0)PD6-PadP$10)") (class "Default")
      (node (ref "U1") (pin "P$10") (pinfunction "(AIN0)PD6_P$10") (pintype "bidirectional"))
    )
    (net (code "121") (name "unconnected-(U1-(INT0)PD2-PadP$32)") (class "Default")
      (node (ref "U1") (pin "P$32") (pinfunction "(INT0)PD2_P$32") (pintype "bidirectional"))
    )
    (net (code "122") (name "unconnected-(U1-(INT1)PD3-PadP$1)") (class "Default")
      (node (ref "U1") (pin "P$1") (pinfunction "(INT1)PD3_P$1") (pintype "bidirectional"))
    )
    (net (code "123") (name "unconnected-(U1-(RXD)PD0-PadP$30)") (class "Default")
      (node (ref "U1") (pin "P$30") (pinfunction "(RXD)PD0_P$30") (pintype "bidirectional"))
    )
    (net (code "124") (name "unconnected-(U1-(SS)PB2-PadP$14)") (class "Default")
      (node (ref "U1") (pin "P$14") (pinfunction "(SS)PB2_P$14") (pintype "bidirectional"))
    )
    (net (code "125") (name "unconnected-(U1-(T1)PD5-PadP$9)") (class "Default")
      (node (ref "U1") (pin "P$9") (pinfunction "(T1)PD5_P$9") (pintype "bidirectional"))
    )
    (net (code "126") (name "unconnected-(U1-(TXD)PD1-PadP$31)") (class "Default")
      (node (ref "U1") (pin "P$31") (pinfunction "(TXD)PD1_P$31") (pintype "bidirectional"))
    )
    (net (code "127") (name "unconnected-(U1-ADC6-PadP$19)") (class "Default")
      (node (ref "U1") (pin "P$19") (pinfunction "ADC6_P$19") (pintype "bidirectional"))
    )
    (net (code "128") (name "unconnected-(U1-ADC7-PadP$22)") (class "Default")
      (node (ref "U1") (pin "P$22") (pinfunction "ADC7_P$22") (pintype "bidirectional"))
    )
  )
)
